# Longboard.net
KiCad netlist of a schematic drawn in EAGLE
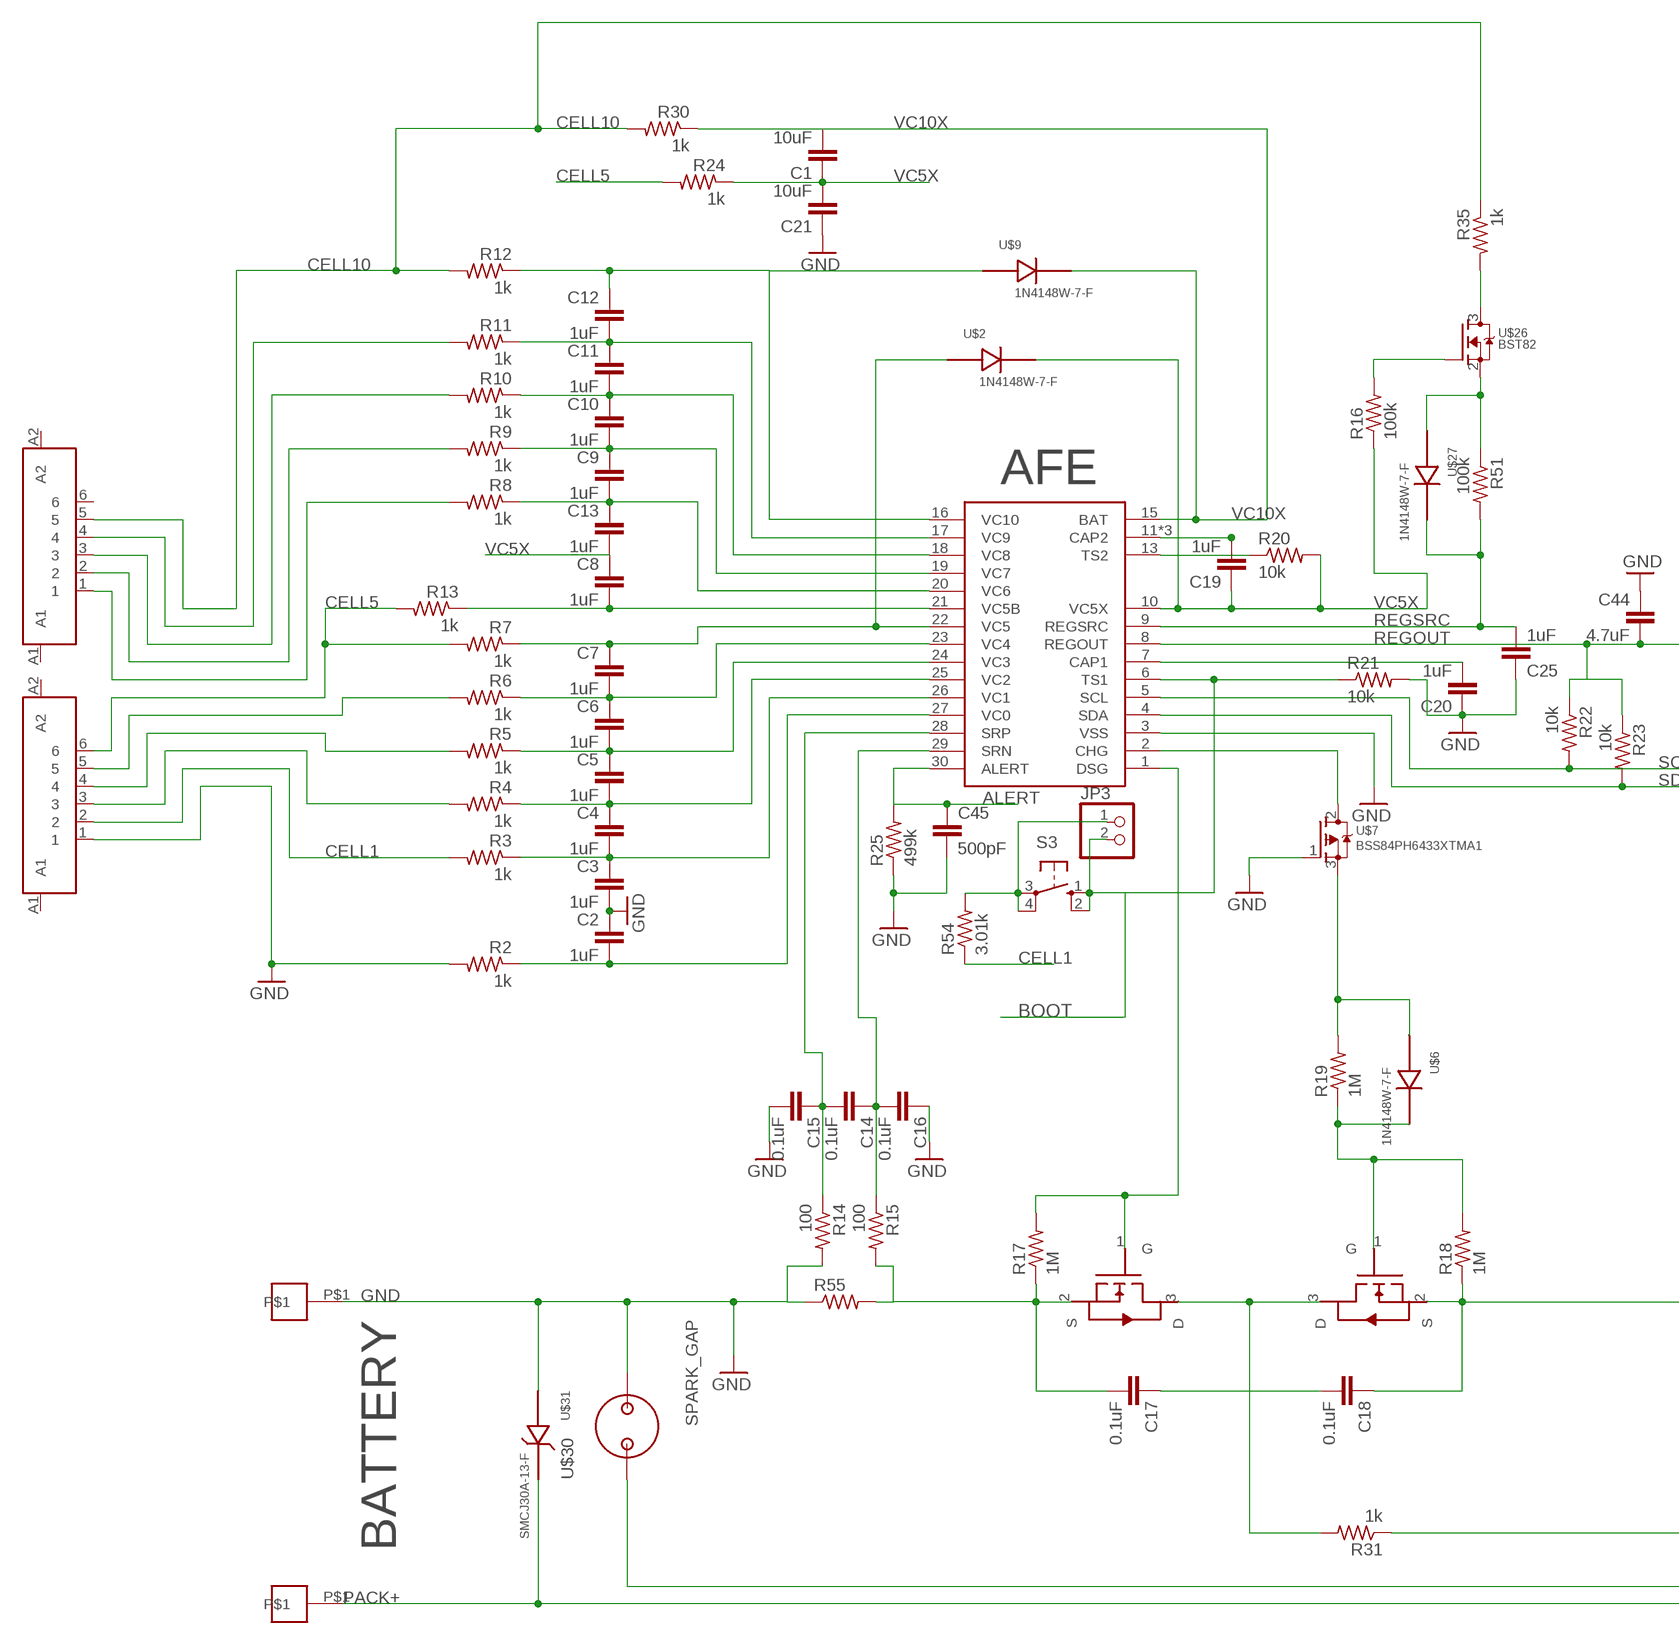
[diagram p0: schematic, sheet 1, part 1 of 2]
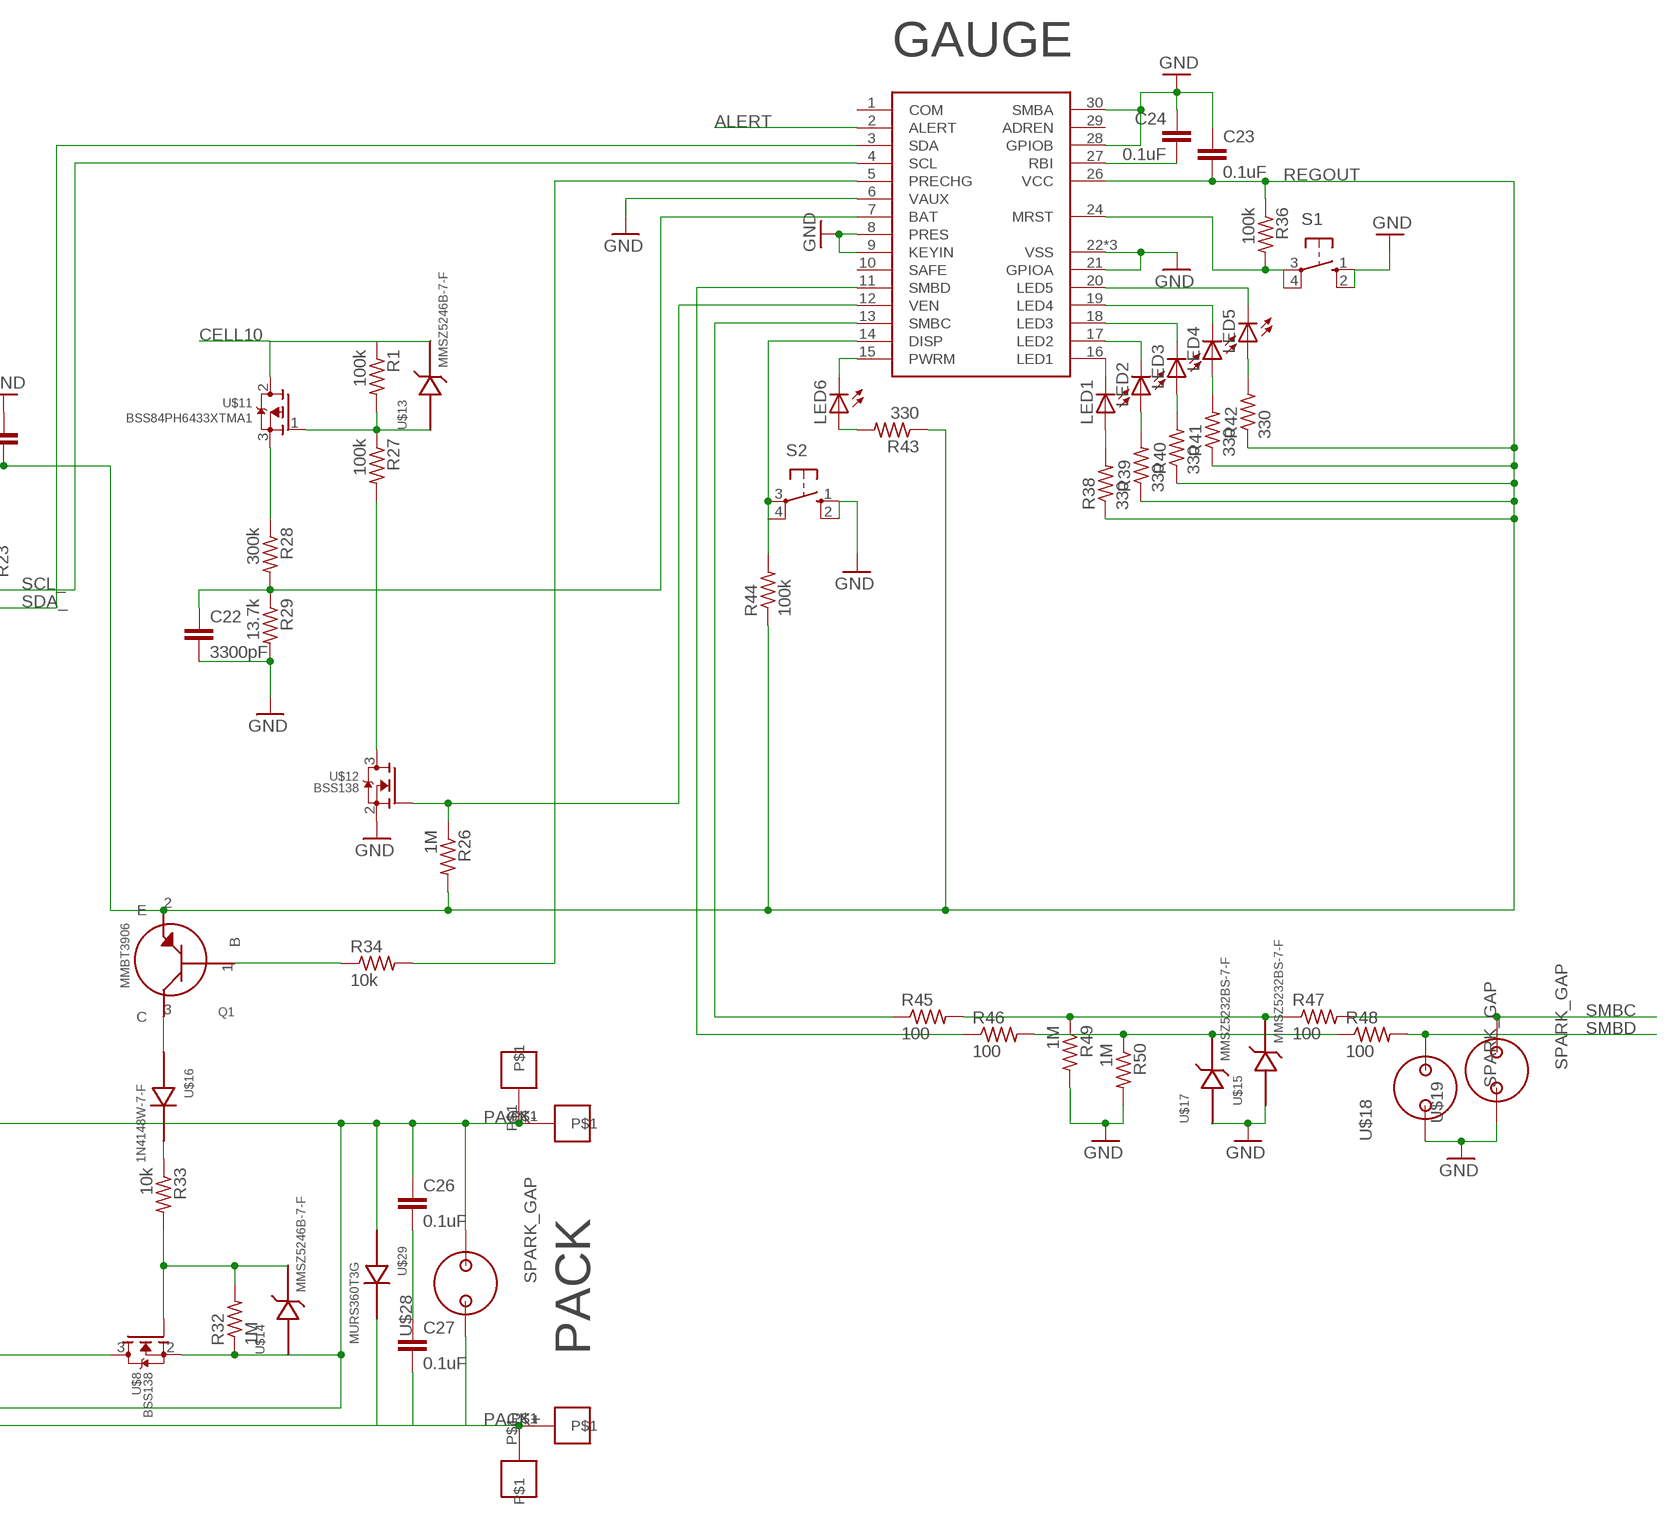
[diagram p1: schematic, sheet 1, part 2 of 2]
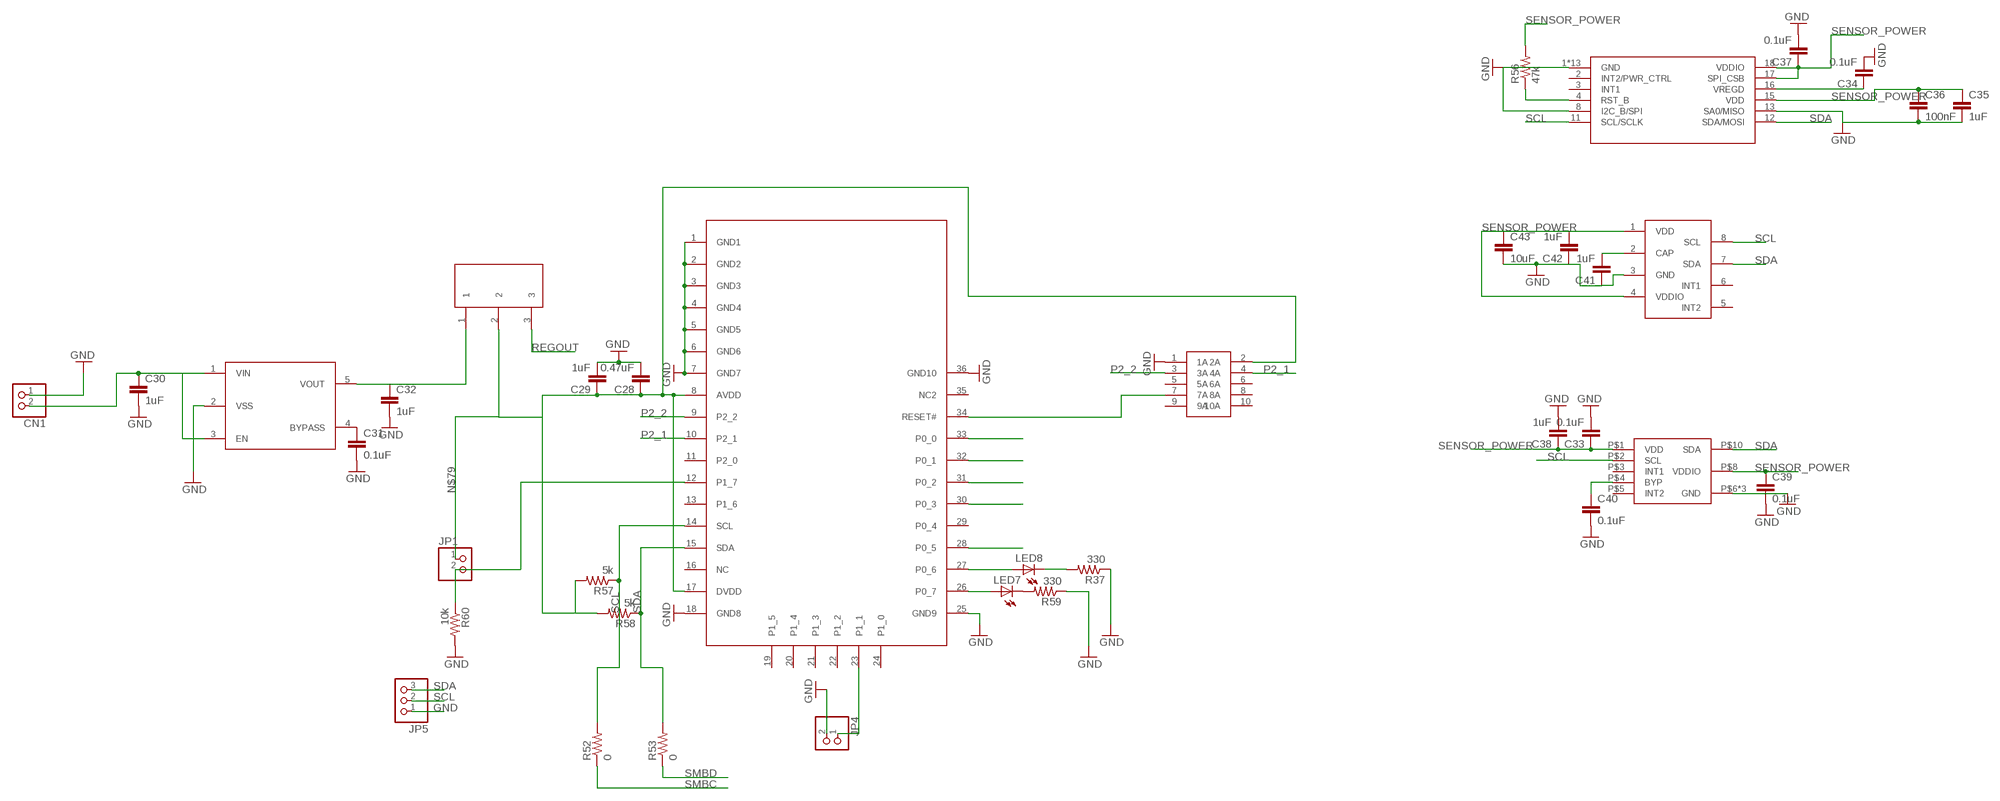
[diagram p2: schematic, sheet 2]

(export (version "E")
  (design (tool "Eeschema 10.0.6"))
  (components
    (comp (ref "C28")
      (value "0.47uF")
      (footprint "eagle-import:C0402")
      (libsource (lib "eagle-import") (part "C-EUC0402"))
    )
    (comp (ref "C29")
      (value "1uF")
      (footprint "eagle-import:C0402")
      (libsource (lib "eagle-import") (part "C-EUC0402"))
    )
    (comp (ref "C30")
      (value "1uF")
      (footprint "eagle-import:C0402")
      (libsource (lib "eagle-import") (part "C-EUC0402"))
    )
    (comp (ref "C31")
      (value "0.1uF")
      (footprint "eagle-import:C0402")
      (libsource (lib "eagle-import") (part "C-EUC0402"))
    )
    (comp (ref "C32")
      (value "1uF")
      (footprint "eagle-import:C0402")
      (libsource (lib "eagle-import") (part "C-EUC0402"))
    )
    (comp (ref "C33")
      (value "0.1uF")
      (footprint "eagle-import:C0402")
      (libsource (lib "eagle-import") (part "C-EUC0402"))
    )
    (comp (ref "C34")
      (value "0.1uF")
      (footprint "eagle-import:C0402")
      (libsource (lib "eagle-import") (part "C-EUC0402"))
    )
    (comp (ref "C35")
      (value "1uF")
      (footprint "eagle-import:C0402")
      (libsource (lib "eagle-import") (part "C-EUC0402"))
    )
    (comp (ref "C36")
      (value "100nF")
      (footprint "eagle-import:C0402")
      (libsource (lib "eagle-import") (part "C-EUC0402"))
    )
    (comp (ref "C37")
      (value "0.1uF")
      (footprint "eagle-import:C0402")
      (libsource (lib "eagle-import") (part "C-EUC0402"))
    )
    (comp (ref "C38")
      (value "1uF")
      (footprint "eagle-import:C0402")
      (libsource (lib "eagle-import") (part "C-EUC0402"))
    )
    (comp (ref "C39")
      (value "0.1uF")
      (footprint "eagle-import:C0402")
      (libsource (lib "eagle-import") (part "C-EUC0402"))
    )
    (comp (ref "C40")
      (value "0.1uF")
      (footprint "eagle-import:C0402")
      (libsource (lib "eagle-import") (part "C-EUC0402"))
    )
    (comp (ref "C41")
      (value "1uF")
      (footprint "eagle-import:C0402")
      (libsource (lib "eagle-import") (part "C-EUC0402"))
    )
    (comp (ref "C42")
      (value "1uF")
      (footprint "eagle-import:C0402")
      (libsource (lib "eagle-import") (part "C-EUC0402"))
    )
    (comp (ref "C43")
      (value "10uF")
      (footprint "eagle-import:C0603")
      (libsource (lib "eagle-import") (part "C-EUC0603"))
    )
    (comp (ref "CN1")
      (value "JST_2PIN-THM")
      (footprint "eagle-import:JST-PH-2-THM")
      (libsource (lib "eagle-import") (part "JST_2PIN-THM"))
    )
    (comp (ref "JP1")
      (value "PINHD-1X2")
      (footprint "eagle-import:1X02")
      (libsource (lib "eagle-import") (part "PINHD-1X2"))
    )
    (comp (ref "JP4")
      (value "PINHD-1X2")
      (footprint "eagle-import:1X02")
      (libsource (lib "eagle-import") (part "PINHD-1X2"))
    )
    (comp (ref "JP5")
      (value "PINHD-1X3")
      (footprint "eagle-import:1X03")
      (libsource (lib "eagle-import") (part "PINHD-1X3"))
    )
    (comp (ref "LED7")
      (value "LEDCHIP-LED0603")
      (footprint "eagle-import:CHIP-LED0603")
      (libsource (lib "eagle-import") (part "LEDCHIP-LED0603"))
    )
    (comp (ref "LED8")
      (value "LEDCHIP-LED0603")
      (footprint "eagle-import:CHIP-LED0603")
      (libsource (lib "eagle-import") (part "LEDCHIP-LED0603"))
    )
    (comp (ref "R37")
      (value "330")
      (footprint "eagle-import:R0402")
      (libsource (lib "eagle-import") (part "R-US_R0402"))
    )
    (comp (ref "R52")
      (value "0")
      (footprint "eagle-import:R0201")
      (libsource (lib "eagle-import") (part "R-US_R0201"))
    )
    (comp (ref "R53")
      (value "0")
      (footprint "eagle-import:R0201")
      (libsource (lib "eagle-import") (part "R-US_R0201"))
    )
    (comp (ref "R56")
      (value "47k")
      (footprint "eagle-import:R0402")
      (libsource (lib "eagle-import") (part "R-US_R0402"))
    )
    (comp (ref "R57")
      (value "5k")
      (footprint "eagle-import:R0402")
      (libsource (lib "eagle-import") (part "R-US_R0402"))
    )
    (comp (ref "R58")
      (value "5k")
      (footprint "eagle-import:R0402")
      (libsource (lib "eagle-import") (part "R-US_R0402"))
    )
    (comp (ref "R59")
      (value "330")
      (footprint "eagle-import:R0402")
      (libsource (lib "eagle-import") (part "R-US_R0402"))
    )
    (comp (ref "R60")
      (value "10k")
      (footprint "eagle-import:R0402")
      (libsource (lib "eagle-import") (part "R-US_R0402"))
    )
    (comp (ref "U$20")
      (value "BLE113")
      (footprint "eagle-import:BLUEGIGA")
      (libsource (lib "eagle-import") (part "BLE113"))
    )
    (comp (ref "U$21")
      (value "LP3985")
      (footprint "eagle-import:SOT23-5L")
      (libsource (lib "eagle-import") (part "LP3985"))
    )
    (comp (ref "U$22")
      (value "RIBBON_10POS_MALE")
      (footprint "eagle-import:RIBBON_10POS_MALE")
      (libsource (lib "eagle-import") (part "RIBBON_10POS_MALE"))
    )
    (comp (ref "U$23")
      (value "SPDT_THRU")
      (footprint "eagle-import:SPDT_THRU")
      (libsource (lib "eagle-import") (part "SPDT_THRU"))
    )
    (comp (ref "U$25")
      (value "MLP3115A2")
      (footprint "eagle-import:MLP3115A2")
      (libsource (lib "eagle-import") (part "MLP3115A2"))
    )
    (comp (ref "U$32")
      (value "MMA8653FC")
      (footprint "eagle-import:10-DFN2X2")
      (libsource (lib "eagle-import") (part "MMA8653FC"))
    )
    (comp (ref "U$34")
      (value "FXAS21002")
      (footprint "eagle-import:FXAS21002")
      (libsource (lib "eagle-import") (part "FXAS21002"))
    )
    (comp (ref "C1")
      (value "10uF")
      (footprint "eagle-import:C1210")
      (libsource (lib "eagle-import") (part "C-EUC1210"))
    )
    (comp (ref "C2")
      (value "1uF")
      (footprint "eagle-import:C0805")
      (libsource (lib "eagle-import") (part "C-EUC0805"))
    )
    (comp (ref "C3")
      (value "1uF")
      (footprint "eagle-import:C0805")
      (libsource (lib "eagle-import") (part "C-EUC0805"))
    )
    (comp (ref "C4")
      (value "1uF")
      (footprint "eagle-import:C0805")
      (libsource (lib "eagle-import") (part "C-EUC0805"))
    )
    (comp (ref "C5")
      (value "1uF")
      (footprint "eagle-import:C0805")
      (libsource (lib "eagle-import") (part "C-EUC0805"))
    )
    (comp (ref "C6")
      (value "1uF")
      (footprint "eagle-import:C0805")
      (libsource (lib "eagle-import") (part "C-EUC0805"))
    )
    (comp (ref "C7")
      (value "1uF")
      (footprint "eagle-import:C0805")
      (libsource (lib "eagle-import") (part "C-EUC0805"))
    )
    (comp (ref "C8")
      (value "1uF")
      (footprint "eagle-import:C0805")
      (libsource (lib "eagle-import") (part "C-EUC0805"))
    )
    (comp (ref "C9")
      (value "1uF")
      (footprint "eagle-import:C0805")
      (libsource (lib "eagle-import") (part "C-EUC0805"))
    )
    (comp (ref "C10")
      (value "1uF")
      (footprint "eagle-import:C0805")
      (libsource (lib "eagle-import") (part "C-EUC0805"))
    )
    (comp (ref "C11")
      (value "1uF")
      (footprint "eagle-import:C0805")
      (libsource (lib "eagle-import") (part "C-EUC0805"))
    )
    (comp (ref "C12")
      (value "1uF")
      (footprint "eagle-import:C0805")
      (libsource (lib "eagle-import") (part "C-EUC0805"))
    )
    (comp (ref "C13")
      (value "1uF")
      (footprint "eagle-import:C0805")
      (libsource (lib "eagle-import") (part "C-EUC0805"))
    )
    (comp (ref "C14")
      (value "0.1uF")
      (footprint "eagle-import:C0805")
      (libsource (lib "eagle-import") (part "C-EUC0805"))
    )
    (comp (ref "C15")
      (value "0.1uF")
      (footprint "eagle-import:C0805")
      (libsource (lib "eagle-import") (part "C-EUC0805"))
    )
    (comp (ref "C16")
      (value "0.1uF")
      (footprint "eagle-import:C0805")
      (libsource (lib "eagle-import") (part "C-EUC0805"))
    )
    (comp (ref "C17")
      (value "0.1uF")
      (footprint "eagle-import:C0805")
      (libsource (lib "eagle-import") (part "C-EUC0805"))
    )
    (comp (ref "C18")
      (value "0.1uF")
      (footprint "eagle-import:C0805")
      (libsource (lib "eagle-import") (part "C-EUC0805"))
    )
    (comp (ref "C19")
      (value "1uF")
      (footprint "eagle-import:C0805")
      (libsource (lib "eagle-import") (part "C-EUC0805"))
    )
    (comp (ref "C20")
      (value "1uF")
      (footprint "eagle-import:C0805")
      (libsource (lib "eagle-import") (part "C-EUC0805"))
    )
    (comp (ref "C21")
      (value "10uF")
      (footprint "eagle-import:C1210")
      (libsource (lib "eagle-import") (part "C-EUC1210"))
    )
    (comp (ref "C22")
      (value "3300pF")
      (footprint "eagle-import:C0402")
      (libsource (lib "eagle-import") (part "C-EUC0402"))
    )
    (comp (ref "C23")
      (value "0.1uF")
      (footprint "eagle-import:C0805")
      (libsource (lib "eagle-import") (part "C-EUC0805"))
    )
    (comp (ref "C24")
      (value "0.1uF")
      (footprint "eagle-import:C0805")
      (libsource (lib "eagle-import") (part "C-EUC0805"))
    )
    (comp (ref "C25")
      (value "1uF")
      (footprint "eagle-import:C0805")
      (libsource (lib "eagle-import") (part "C-EUC0805"))
    )
    (comp (ref "C26")
      (value "0.1uF")
      (footprint "eagle-import:C0805")
      (libsource (lib "eagle-import") (part "C-EUC0805"))
    )
    (comp (ref "C27")
      (value "0.1uF")
      (footprint "eagle-import:C0805")
      (libsource (lib "eagle-import") (part "C-EUC0805"))
    )
    (comp (ref "C44")
      (value "4.7uF")
      (footprint "eagle-import:C0805")
      (libsource (lib "eagle-import") (part "C-EUC0805"))
    )
    (comp (ref "C45")
      (value "500pF")
      (footprint "eagle-import:C0603")
      (libsource (lib "eagle-import") (part "C-EUC0603"))
    )
    (comp (ref "JP3")
      (value "PINHD-1X2")
      (footprint "eagle-import:1X02")
      (libsource (lib "eagle-import") (part "PINHD-1X2"))
    )
    (comp (ref "LED1")
      (value "LEDCHIPLED_0603")
      (footprint "eagle-import:CHIPLED_0603")
      (libsource (lib "eagle-import") (part "LEDCHIPLED_0603"))
    )
    (comp (ref "LED2")
      (value "LEDCHIPLED_0603")
      (footprint "eagle-import:CHIPLED_0603")
      (libsource (lib "eagle-import") (part "LEDCHIPLED_0603"))
    )
    (comp (ref "LED3")
      (value "LEDCHIPLED_0603")
      (footprint "eagle-import:CHIPLED_0603")
      (libsource (lib "eagle-import") (part "LEDCHIPLED_0603"))
    )
    (comp (ref "LED4")
      (value "LEDCHIPLED_0603")
      (footprint "eagle-import:CHIPLED_0603")
      (libsource (lib "eagle-import") (part "LEDCHIPLED_0603"))
    )
    (comp (ref "LED5")
      (value "LEDCHIPLED_0603")
      (footprint "eagle-import:CHIPLED_0603")
      (libsource (lib "eagle-import") (part "LEDCHIPLED_0603"))
    )
    (comp (ref "LED6")
      (value "LEDCHIPLED_0603")
      (footprint "eagle-import:CHIPLED_0603")
      (libsource (lib "eagle-import") (part "LEDCHIPLED_0603"))
    )
    (comp (ref "Q1")
      (value "MMBT3906")
      (footprint "eagle-import:SOT23-3")
      (libsource (lib "eagle-import") (part "MMBT3906"))
    )
    (comp (ref "R1")
      (value "100k")
      (footprint "eagle-import:R0805")
      (libsource (lib "eagle-import") (part "R-US_R0805"))
    )
    (comp (ref "R2")
      (value "1k")
      (footprint "eagle-import:R1206")
      (libsource (lib "eagle-import") (part "R-US_R1206"))
    )
    (comp (ref "R3")
      (value "1k")
      (footprint "eagle-import:R1206")
      (libsource (lib "eagle-import") (part "R-US_R1206"))
    )
    (comp (ref "R4")
      (value "1k")
      (footprint "eagle-import:R1206")
      (libsource (lib "eagle-import") (part "R-US_R1206"))
    )
    (comp (ref "R5")
      (value "1k")
      (footprint "eagle-import:R1206")
      (libsource (lib "eagle-import") (part "R-US_R1206"))
    )
    (comp (ref "R6")
      (value "1k")
      (footprint "eagle-import:R1206")
      (libsource (lib "eagle-import") (part "R-US_R1206"))
    )
    (comp (ref "R7")
      (value "1k")
      (footprint "eagle-import:R1206")
      (libsource (lib "eagle-import") (part "R-US_R1206"))
    )
    (comp (ref "R8")
      (value "1k")
      (footprint "eagle-import:R1206")
      (libsource (lib "eagle-import") (part "R-US_R1206"))
    )
    (comp (ref "R9")
      (value "1k")
      (footprint "eagle-import:R1206")
      (libsource (lib "eagle-import") (part "R-US_R1206"))
    )
    (comp (ref "R10")
      (value "1k")
      (footprint "eagle-import:R1206")
      (libsource (lib "eagle-import") (part "R-US_R1206"))
    )
    (comp (ref "R11")
      (value "1k")
      (footprint "eagle-import:R1206")
      (libsource (lib "eagle-import") (part "R-US_R1206"))
    )
    (comp (ref "R12")
      (value "1k")
      (footprint "eagle-import:R1206")
      (libsource (lib "eagle-import") (part "R-US_R1206"))
    )
    (comp (ref "R13")
      (value "1k")
      (footprint "eagle-import:R1206")
      (libsource (lib "eagle-import") (part "R-US_R1206"))
    )
    (comp (ref "R14")
      (value "100")
      (footprint "eagle-import:R0805")
      (libsource (lib "eagle-import") (part "R-US_R0805"))
    )
    (comp (ref "R15")
      (value "100")
      (footprint "eagle-import:R0805")
      (libsource (lib "eagle-import") (part "R-US_R0805"))
    )
    (comp (ref "R16")
      (value "100k")
      (footprint "eagle-import:R0805")
      (libsource (lib "eagle-import") (part "R-US_R0805"))
    )
    (comp (ref "R17")
      (value "1M")
      (footprint "eagle-import:R1206")
      (libsource (lib "eagle-import") (part "R-US_R1206"))
    )
    (comp (ref "R18")
      (value "1M")
      (footprint "eagle-import:R1206")
      (libsource (lib "eagle-import") (part "R-US_R1206"))
    )
    (comp (ref "R19")
      (value "1M")
      (footprint "eagle-import:R1206")
      (libsource (lib "eagle-import") (part "R-US_R1206"))
    )
    (comp (ref "R20")
      (value "10k")
      (footprint "eagle-import:R0805")
      (libsource (lib "eagle-import") (part "R-US_R0805"))
    )
    (comp (ref "R21")
      (value "10k")
      (footprint "eagle-import:R0805")
      (libsource (lib "eagle-import") (part "R-US_R0805"))
    )
    (comp (ref "R22")
      (value "10k")
      (footprint "eagle-import:R0805")
      (libsource (lib "eagle-import") (part "R-US_R0805"))
    )
    (comp (ref "R23")
      (value "10k")
      (footprint "eagle-import:R0805")
      (libsource (lib "eagle-import") (part "R-US_R0805"))
    )
    (comp (ref "R24")
      (value "1k")
      (footprint "eagle-import:R1206")
      (libsource (lib "eagle-import") (part "R-US_R1206"))
    )
    (comp (ref "R25")
      (value "499k")
      (footprint "eagle-import:R0603")
      (libsource (lib "eagle-import") (part "R-US_R0603"))
    )
    (comp (ref "R26")
      (value "1M")
      (footprint "eagle-import:R1206")
      (libsource (lib "eagle-import") (part "R-US_R1206"))
    )
    (comp (ref "R27")
      (value "100k")
      (footprint "eagle-import:R0805")
      (libsource (lib "eagle-import") (part "R-US_R0805"))
    )
    (comp (ref "R28")
      (value "300k")
      (footprint "eagle-import:R0805")
      (libsource (lib "eagle-import") (part "R-US_R0805"))
    )
    (comp (ref "R29")
      (value "13.7k")
      (footprint "eagle-import:R0805")
      (libsource (lib "eagle-import") (part "R-US_R0805"))
    )
    (comp (ref "R30")
      (value "1k")
      (footprint "eagle-import:R1206")
      (libsource (lib "eagle-import") (part "R-US_R1206"))
    )
    (comp (ref "R31")
      (value "1k")
      (footprint "eagle-import:R2512")
      (libsource (lib "eagle-import") (part "R-US_R2512"))
    )
    (comp (ref "R32")
      (value "1M")
      (footprint "eagle-import:R1206")
      (libsource (lib "eagle-import") (part "R-US_R1206"))
    )
    (comp (ref "R33")
      (value "10k")
      (footprint "eagle-import:R0805")
      (libsource (lib "eagle-import") (part "R-US_R0805"))
    )
    (comp (ref "R34")
      (value "10k")
      (footprint "eagle-import:R0805")
      (libsource (lib "eagle-import") (part "R-US_R0805"))
    )
    (comp (ref "R35")
      (value "1k")
      (footprint "eagle-import:R1206")
      (libsource (lib "eagle-import") (part "R-US_R1206"))
    )
    (comp (ref "R36")
      (value "100k")
      (footprint "eagle-import:R0805")
      (libsource (lib "eagle-import") (part "R-US_R0805"))
    )
    (comp (ref "R38")
      (value "330")
      (footprint "eagle-import:R0402")
      (libsource (lib "eagle-import") (part "R-US_R0402"))
    )
    (comp (ref "R39")
      (value "330")
      (footprint "eagle-import:R0402")
      (libsource (lib "eagle-import") (part "R-US_R0402"))
    )
    (comp (ref "R40")
      (value "330")
      (footprint "eagle-import:R0402")
      (libsource (lib "eagle-import") (part "R-US_R0402"))
    )
    (comp (ref "R41")
      (value "330")
      (footprint "eagle-import:R0402")
      (libsource (lib "eagle-import") (part "R-US_R0402"))
    )
    (comp (ref "R42")
      (value "330")
      (footprint "eagle-import:R0402")
      (libsource (lib "eagle-import") (part "R-US_R0402"))
    )
    (comp (ref "R43")
      (value "330")
      (footprint "eagle-import:R0402")
      (libsource (lib "eagle-import") (part "R-US_R0402"))
    )
    (comp (ref "R44")
      (value "100k")
      (footprint "eagle-import:R0402")
      (libsource (lib "eagle-import") (part "R-US_R0402"))
    )
    (comp (ref "R45")
      (value "100")
      (footprint "eagle-import:R0805")
      (libsource (lib "eagle-import") (part "R-US_R0805"))
    )
    (comp (ref "R46")
      (value "100")
      (footprint "eagle-import:R0805")
      (libsource (lib "eagle-import") (part "R-US_R0805"))
    )
    (comp (ref "R47")
      (value "100")
      (footprint "eagle-import:R0805")
      (libsource (lib "eagle-import") (part "R-US_R0805"))
    )
    (comp (ref "R48")
      (value "100")
      (footprint "eagle-import:R0805")
      (libsource (lib "eagle-import") (part "R-US_R0805"))
    )
    (comp (ref "R49")
      (value "1M")
      (footprint "eagle-import:R1206")
      (libsource (lib "eagle-import") (part "R-US_R1206"))
    )
    (comp (ref "R50")
      (value "1M")
      (footprint "eagle-import:R1206")
      (libsource (lib "eagle-import") (part "R-US_R1206"))
    )
    (comp (ref "R51")
      (value "100k")
      (footprint "eagle-import:R0805")
      (libsource (lib "eagle-import") (part "R-US_R0805"))
    )
    (comp (ref "R54")
      (value "3.01k")
      (footprint "eagle-import:R1206")
      (libsource (lib "eagle-import") (part "R-US_R1206"))
    )
    (comp (ref "R55")
      (value "R-US_R2512")
      (footprint "eagle-import:R2512")
      (libsource (lib "eagle-import") (part "R-US_R2512"))
    )
    (comp (ref "S1")
      (value "10-XX")
      (footprint "eagle-import:B3F-10XX")
      (fields (field (name "MPN") "B3F-1000"))
      (libsource (lib "eagle-import") (part "10-XX"))
    )
    (comp (ref "S2")
      (value "10-XX")
      (footprint "eagle-import:B3F-10XX")
      (fields (field (name "MPN") "B3F-1000"))
      (libsource (lib "eagle-import") (part "10-XX"))
    )
    (comp (ref "S3")
      (value "10-XX")
      (footprint "eagle-import:B3F-10XX")
      (fields (field (name "MPN") "B3F-1000"))
      (libsource (lib "eagle-import") (part "10-XX"))
    )
    (comp (ref "U$1")
      (value "BQ76930")
      (footprint "eagle-import:SOIC-30")
      (libsource (lib "eagle-import") (part "BQ76930"))
    )
    (comp (ref "U$2")
      (value "1N4148W-7-F")
      (footprint "eagle-import:SOD-123")
      (libsource (lib "eagle-import") (part "1N4148W-7-F"))
    )
    (comp (ref "U$3")
      (value "PAD")
      (footprint "eagle-import:PAD")
      (libsource (lib "eagle-import") (part "PAD"))
    )
    (comp (ref "U$4")
      (value "AOB290L")
      (footprint "eagle-import:TO-263")
      (libsource (lib "eagle-import") (part "AOB290L"))
    )
    (comp (ref "U$5")
      (value "AOB290L")
      (footprint "eagle-import:TO-263")
      (libsource (lib "eagle-import") (part "AOB290L"))
    )
    (comp (ref "U$6")
      (value "1N4148W-7-F")
      (footprint "eagle-import:SOD-123")
      (libsource (lib "eagle-import") (part "1N4148W-7-F"))
    )
    (comp (ref "U$7")
      (value "BSS84PH6433XTMA1")
      (footprint "eagle-import:SOT23-3")
      (libsource (lib "eagle-import") (part "BSS84PH6433XTMA1"))
    )
    (comp (ref "U$8")
      (value "BSS138")
      (footprint "eagle-import:SOT23-3")
      (libsource (lib "eagle-import") (part "BSS138"))
    )
    (comp (ref "U$9")
      (value "1N4148W-7-F")
      (footprint "eagle-import:SOD-123")
      (libsource (lib "eagle-import") (part "1N4148W-7-F"))
    )
    (comp (ref "U$10")
      (value "BQ78350-R1")
      (footprint "eagle-import:SOIC-30")
      (libsource (lib "eagle-import") (part "BQ78350-R1"))
    )
    (comp (ref "U$11")
      (value "BSS84PH6433XTMA1")
      (footprint "eagle-import:SOT23-3")
      (libsource (lib "eagle-import") (part "BSS84PH6433XTMA1"))
    )
    (comp (ref "U$12")
      (value "BSS138")
      (footprint "eagle-import:SOT23-3")
      (libsource (lib "eagle-import") (part "BSS138"))
    )
    (comp (ref "U$13")
      (value "MMSZ5246B-7-F")
      (footprint "eagle-import:SOD-123")
      (libsource (lib "eagle-import") (part "MMSZ5246B-7-F"))
    )
    (comp (ref "U$14")
      (value "MMSZ5246B-7-F")
      (footprint "eagle-import:SOD-123")
      (libsource (lib "eagle-import") (part "MMSZ5246B-7-F"))
    )
    (comp (ref "U$15")
      (value "MMSZ5232BS-7-F")
      (footprint "eagle-import:SOD-323F")
      (libsource (lib "eagle-import") (part "MMSZ5232BS-7-F"))
    )
    (comp (ref "U$16")
      (value "1N4148W-7-F")
      (footprint "eagle-import:SOD-123")
      (libsource (lib "eagle-import") (part "1N4148W-7-F"))
    )
    (comp (ref "U$17")
      (value "MMSZ5232BS-7-F")
      (footprint "eagle-import:SOD-323F")
      (libsource (lib "eagle-import") (part "MMSZ5232BS-7-F"))
    )
    (comp (ref "U$18")
      (value "SPARK_GAP")
      (footprint "eagle-import:SPARK_GAP")
      (libsource (lib "eagle-import") (part "SPARK_GAP"))
    )
    (comp (ref "U$19")
      (value "SPARK_GAP")
      (footprint "eagle-import:SPARK_GAP")
      (libsource (lib "eagle-import") (part "SPARK_GAP"))
    )
    (comp (ref "U$24")
      (value "JST_6PIN")
      (footprint "eagle-import:JST_6PIN")
      (libsource (lib "eagle-import") (part "JST_6PIN"))
    )
    (comp (ref "U$26")
      (value "BST82")
      (footprint "eagle-import:SOT23-3")
      (libsource (lib "eagle-import") (part "BST82"))
    )
    (comp (ref "U$27")
      (value "1N4148W-7-F")
      (footprint "eagle-import:SOD-123")
      (libsource (lib "eagle-import") (part "1N4148W-7-F"))
    )
    (comp (ref "U$28")
      (value "SPARK_GAP")
      (footprint "eagle-import:SPARK_GAP")
      (libsource (lib "eagle-import") (part "SPARK_GAP"))
    )
    (comp (ref "U$29")
      (value "MURS360T3G")
      (footprint "eagle-import:SMC(DO-214AB)")
      (libsource (lib "eagle-import") (part "MURS360T3G"))
    )
    (comp (ref "U$30")
      (value "SPARK_GAP")
      (footprint "eagle-import:SPARK_GAP")
      (libsource (lib "eagle-import") (part "SPARK_GAP"))
    )
    (comp (ref "U$31")
      (value "SMCJ30A-13-F")
      (footprint "eagle-import:SMB(DO-214AA)")
      (libsource (lib "eagle-import") (part "SMCJ30A-13-F"))
    )
    (comp (ref "U$33")
      (value "JST_6PIN")
      (footprint "eagle-import:JST_6PIN")
      (libsource (lib "eagle-import") (part "JST_6PIN"))
    )
    (comp (ref "U$35")
      (value "PAD")
      (footprint "eagle-import:PAD")
      (libsource (lib "eagle-import") (part "PAD"))
    )
    (comp (ref "U$36")
      (value "PAD")
      (footprint "eagle-import:PAD")
      (libsource (lib "eagle-import") (part "PAD"))
    )
    (comp (ref "U$37")
      (value "PAD")
      (footprint "eagle-import:PAD")
      (libsource (lib "eagle-import") (part "PAD"))
    )
    (comp (ref "U$38")
      (value "PAD")
      (footprint "eagle-import:PAD")
      (libsource (lib "eagle-import") (part "PAD"))
    )
    (comp (ref "U$39")
      (value "PAD")
      (footprint "eagle-import:PAD")
      (libsource (lib "eagle-import") (part "PAD"))
    )
  )
  (nets
    (net (code "1") (name "ALERT") (class "Default")
      (node (ref "C45") (pin "1") (pinfunction "1_1") (pintype "passive"))
      (node (ref "R25") (pin "2") (pinfunction "2_2") (pintype "passive"))
      (node (ref "U$1") (pin "30") (pinfunction "ALERT_30") (pintype "bidirectional"))
      (node (ref "U$10") (pin "2") (pinfunction "ALERT_2") (pintype "bidirectional"))
    )
    (net (code "2") (name "BOOT") (class "Default")
      (node (ref "JP3") (pin "2") (pinfunction "2_2") (pintype "passive"))
      (node (ref "R21") (pin "1") (pinfunction "1_1") (pintype "passive"))
      (node (ref "S3") (pin "1") (pinfunction "S_1") (pintype "passive"))
      (node (ref "S3") (pin "2") (pinfunction "S1_2") (pintype "passive"))
      (node (ref "U$1") (pin "6") (pinfunction "TS1_6") (pintype "bidirectional"))
    )
    (net (code "3") (name "CELL1") (class "Default")
      (node (ref "R3") (pin "2") (pinfunction "2_2") (pintype "passive"))
      (node (ref "R54") (pin "1") (pinfunction "1_1") (pintype "passive"))
      (node (ref "U$33") (pin "2") (pinfunction "2_2") (pintype "bidirectional"))
    )
    (net (code "4") (name "CELL5") (class "Default")
      (node (ref "R13") (pin "2") (pinfunction "2_2") (pintype "passive"))
      (node (ref "R24") (pin "2") (pinfunction "2_2") (pintype "passive"))
      (node (ref "R7") (pin "2") (pinfunction "2_2") (pintype "passive"))
      (node (ref "U$33") (pin "6") (pinfunction "6_6") (pintype "bidirectional"))
    )
    (net (code "5") (name "CELL10") (class "Default")
      (node (ref "R1") (pin "1") (pinfunction "1_1") (pintype "passive"))
      (node (ref "R12") (pin "2") (pinfunction "2_2") (pintype "passive"))
      (node (ref "R30") (pin "2") (pinfunction "2_2") (pintype "passive"))
      (node (ref "R35") (pin "1") (pinfunction "1_1") (pintype "passive"))
      (node (ref "U$11") (pin "2") (pinfunction "S_2") (pintype "bidirectional"))
      (node (ref "U$13") (pin "P$2") (pinfunction "2_P$2") (pintype "bidirectional"))
      (node (ref "U$24") (pin "5") (pinfunction "5_5") (pintype "bidirectional"))
    )
    (net (code "6") (name "GND") (class "Default")
      (node (ref "C15") (pin "2") (pinfunction "2_2") (pintype "passive"))
      (node (ref "C16") (pin "1") (pinfunction "1_1") (pintype "passive"))
      (node (ref "C2") (pin "1") (pinfunction "1_1") (pintype "passive"))
      (node (ref "C20") (pin "1") (pinfunction "1_1") (pintype "passive"))
      (node (ref "C21") (pin "1") (pinfunction "1_1") (pintype "passive"))
      (node (ref "C22") (pin "2") (pinfunction "2_2") (pintype "passive"))
      (node (ref "C23") (pin "1") (pinfunction "1_1") (pintype "passive"))
      (node (ref "C24") (pin "1") (pinfunction "1_1") (pintype "passive"))
      (node (ref "C25") (pin "1") (pinfunction "1_1") (pintype "passive"))
      (node (ref "C28") (pin "2") (pinfunction "2_2") (pintype "passive"))
      (node (ref "C29") (pin "2") (pinfunction "2_2") (pintype "passive"))
      (node (ref "C3") (pin "2") (pinfunction "2_2") (pintype "passive"))
      (node (ref "C30") (pin "2") (pinfunction "2_2") (pintype "passive"))
      (node (ref "C31") (pin "2") (pinfunction "2_2") (pintype "passive"))
      (node (ref "C32") (pin "2") (pinfunction "2_2") (pintype "passive"))
      (node (ref "C33") (pin "2") (pinfunction "2_2") (pintype "passive"))
      (node (ref "C34") (pin "2") (pinfunction "2_2") (pintype "passive"))
      (node (ref "C35") (pin "2") (pinfunction "2_2") (pintype "passive"))
      (node (ref "C36") (pin "2") (pinfunction "2_2") (pintype "passive"))
      (node (ref "C37") (pin "2") (pinfunction "2_2") (pintype "passive"))
      (node (ref "C38") (pin "2") (pinfunction "2_2") (pintype "passive"))
      (node (ref "C39") (pin "2") (pinfunction "2_2") (pintype "passive"))
      (node (ref "C40") (pin "2") (pinfunction "2_2") (pintype "passive"))
      (node (ref "C41") (pin "1") (pinfunction "1_1") (pintype "passive"))
      (node (ref "C42") (pin "1") (pinfunction "1_1") (pintype "passive"))
      (node (ref "C43") (pin "2") (pinfunction "2_2") (pintype "passive"))
      (node (ref "C44") (pin "1") (pinfunction "1_1") (pintype "passive"))
      (node (ref "C45") (pin "2") (pinfunction "2_2") (pintype "passive"))
      (node (ref "CN1") (pin "1") (pinfunction "2_1") (pintype "passive"))
      (node (ref "JP4") (pin "2") (pinfunction "2_2") (pintype "passive"))
      (node (ref "JP5") (pin "1") (pinfunction "1_1") (pintype "passive"))
      (node (ref "R14") (pin "2") (pinfunction "2_2") (pintype "passive"))
      (node (ref "R2") (pin "2") (pinfunction "2_2") (pintype "passive"))
      (node (ref "R21") (pin "2") (pinfunction "2_2") (pintype "passive"))
      (node (ref "R25") (pin "1") (pinfunction "1_1") (pintype "passive"))
      (node (ref "R29") (pin "2") (pinfunction "2_2") (pintype "passive"))
      (node (ref "R37") (pin "1") (pinfunction "1_1") (pintype "passive"))
      (node (ref "R49") (pin "2") (pinfunction "2_2") (pintype "passive"))
      (node (ref "R50") (pin "2") (pinfunction "2_2") (pintype "passive"))
      (node (ref "R55") (pin "1") (pinfunction "1_1") (pintype "passive"))
      (node (ref "R59") (pin "1") (pinfunction "1_1") (pintype "passive"))
      (node (ref "R60") (pin "2") (pinfunction "2_2") (pintype "passive"))
      (node (ref "S1") (pin "1") (pinfunction "S_1") (pintype "passive"))
      (node (ref "S1") (pin "2") (pinfunction "S1_2") (pintype "passive"))
      (node (ref "S2") (pin "1") (pinfunction "S_1") (pintype "passive"))
      (node (ref "S2") (pin "2") (pinfunction "S1_2") (pintype "passive"))
      (node (ref "U$1") (pin "3") (pinfunction "VSS_3") (pintype "bidirectional"))
      (node (ref "U$10") (pin "21") (pinfunction "GPIOA_21") (pintype "bidirectional"))
      (node (ref "U$10") (pin "22") (pinfunction "VSS_22") (pintype "bidirectional"))
      (node (ref "U$10") (pin "23") (pinfunction "VSS_23") (pintype "bidirectional"))
      (node (ref "U$10") (pin "25") (pinfunction "VSS_25") (pintype "bidirectional"))
      (node (ref "U$10") (pin "28") (pinfunction "GPIOB_28") (pintype "bidirectional"))
      (node (ref "U$10") (pin "30") (pinfunction "SMBA_30") (pintype "bidirectional"))
      (node (ref "U$10") (pin "6") (pinfunction "VAUX_6") (pintype "bidirectional"))
      (node (ref "U$10") (pin "8") (pinfunction "PRES_8") (pintype "bidirectional"))
      (node (ref "U$10") (pin "9") (pinfunction "KEYIN_9") (pintype "bidirectional"))
      (node (ref "U$12") (pin "2") (pinfunction "S_2") (pintype "bidirectional"))
      (node (ref "U$15") (pin "1") (pinfunction "1_1") (pintype "bidirectional"))
      (node (ref "U$17") (pin "1") (pinfunction "1_1") (pintype "bidirectional"))
      (node (ref "U$18") (pin "P$1") (pinfunction "P$1_P$1") (pintype "bidirectional"))
      (node (ref "U$19") (pin "P$1") (pinfunction "P$1_P$1") (pintype "bidirectional"))
      (node (ref "U$20") (pin "1") (pinfunction "GND1_1") (pintype "bidirectional"))
      (node (ref "U$20") (pin "18") (pinfunction "GND8_18") (pintype "bidirectional"))
      (node (ref "U$20") (pin "2") (pinfunction "GND2_2") (pintype "bidirectional"))
      (node (ref "U$20") (pin "25") (pinfunction "GND9_25") (pintype "bidirectional"))
      (node (ref "U$20") (pin "3") (pinfunction "GND3_3") (pintype "bidirectional"))
      (node (ref "U$20") (pin "36") (pinfunction "GND10_36") (pintype "bidirectional"))
      (node (ref "U$20") (pin "4") (pinfunction "GND4_4") (pintype "bidirectional"))
      (node (ref "U$20") (pin "5") (pinfunction "GND5_5") (pintype "bidirectional"))
      (node (ref "U$20") (pin "6") (pinfunction "GND6_6") (pintype "bidirectional"))
      (node (ref "U$20") (pin "7") (pinfunction "GND7_7") (pintype "bidirectional"))
      (node (ref "U$21") (pin "2") (pinfunction "VSS_2") (pintype "bidirectional"))
      (node (ref "U$22") (pin "1") (pinfunction "1A_1") (pintype "bidirectional"))
      (node (ref "U$25") (pin "3") (pinfunction "GND_3") (pintype "bidirectional"))
      (node (ref "U$3") (pin "P$1") (pinfunction "P$1_P$1") (pintype "bidirectional"))
      (node (ref "U$30") (pin "P$2") (pinfunction "P$2_P$2") (pintype "bidirectional"))
      (node (ref "U$31") (pin "P$1") (pinfunction "1_P$1") (pintype "bidirectional"))
      (node (ref "U$32") (pin "P$6") (pinfunction "GND_P$6") (pintype "bidirectional"))
      (node (ref "U$32") (pin "P$7") (pinfunction "GND_P$7") (pintype "bidirectional"))
      (node (ref "U$32") (pin "P$9") (pinfunction "GND_P$9") (pintype "bidirectional"))
      (node (ref "U$33") (pin "1") (pinfunction "1_1") (pintype "bidirectional"))
      (node (ref "U$34") (pin "1") (pinfunction "GND_1") (pintype "bidirectional"))
      (node (ref "U$34") (pin "10") (pinfunction "GND_10") (pintype "bidirectional"))
      (node (ref "U$34") (pin "13") (pinfunction "SA0/MISO_13") (pintype "bidirectional"))
      (node (ref "U$34") (pin "14") (pinfunction "GND_14") (pintype "bidirectional"))
      (node (ref "U$34") (pin "19") (pinfunction "GND_19") (pintype "bidirectional"))
      (node (ref "U$34") (pin "20") (pinfunction "GND_20") (pintype "bidirectional"))
      (node (ref "U$34") (pin "21") (pinfunction "GND_21") (pintype "bidirectional"))
      (node (ref "U$34") (pin "22") (pinfunction "GND_22") (pintype "bidirectional"))
      (node (ref "U$34") (pin "23") (pinfunction "GND_23") (pintype "bidirectional"))
      (node (ref "U$34") (pin "24") (pinfunction "GND_24") (pintype "bidirectional"))
      (node (ref "U$34") (pin "5") (pinfunction "GND_5") (pintype "bidirectional"))
      (node (ref "U$34") (pin "6") (pinfunction "GND_6") (pintype "bidirectional"))
      (node (ref "U$34") (pin "7") (pinfunction "GND_7") (pintype "bidirectional"))
      (node (ref "U$34") (pin "8") (pinfunction "I2C_B/SPI_8") (pintype "bidirectional"))
      (node (ref "U$34") (pin "9") (pinfunction "GND_9") (pintype "bidirectional"))
      (node (ref "U$7") (pin "1") (pinfunction "G_1") (pintype "bidirectional"))
    )
    (net (code "7") (name "N$79") (class "Default")
      (node (ref "C28") (pin "1") (pinfunction "1_1") (pintype "passive"))
      (node (ref "C29") (pin "1") (pinfunction "1_1") (pintype "passive"))
      (node (ref "JP1") (pin "1") (pinfunction "1_1") (pintype "passive"))
      (node (ref "R57") (pin "2") (pinfunction "2_2") (pintype "passive"))
      (node (ref "R58") (pin "2") (pinfunction "2_2") (pintype "passive"))
      (node (ref "U$20") (pin "17") (pinfunction "DVDD_17") (pintype "bidirectional"))
      (node (ref "U$20") (pin "8") (pinfunction "AVDD_8") (pintype "bidirectional"))
      (node (ref "U$22") (pin "2") (pinfunction "2A_2") (pintype "bidirectional"))
      (node (ref "U$23") (pin "2") (pinfunction "2_2") (pintype "bidirectional"))
    )
    (net (code "8") (name "Net-(C17-Pad1)") (class "Default")
      (node (ref "C17") (pin "1") (pinfunction "1_1") (pintype "passive"))
      (node (ref "C18") (pin "2") (pinfunction "2_2") (pintype "passive"))
    )
    (net (code "9") (name "Net-(C19-Pad2)") (class "Default")
      (node (ref "C19") (pin "2") (pinfunction "2_2") (pintype "passive"))
      (node (ref "U$1") (pin "11") (pinfunction "CAP2_11") (pintype "bidirectional"))
      (node (ref "U$1") (pin "12") (pinfunction "CAP2_12") (pintype "bidirectional"))
      (node (ref "U$1") (pin "14") (pinfunction "CAP2_14") (pintype "bidirectional"))
    )
    (net (code "10") (name "Net-(C26-Pad2)") (class "Default")
      (node (ref "C26") (pin "2") (pinfunction "2_2") (pintype "passive"))
      (node (ref "C27") (pin "1") (pinfunction "1_1") (pintype "passive"))
    )
    (net (code "11") (name "Net-(CN1-1)") (class "Default")
      (node (ref "C30") (pin "1") (pinfunction "1_1") (pintype "passive"))
      (node (ref "CN1") (pin "2") (pinfunction "1_2") (pintype "passive"))
      (node (ref "U$21") (pin "1") (pinfunction "VIN_1") (pintype "bidirectional"))
      (node (ref "U$21") (pin "3") (pinfunction "EN_3") (pintype "bidirectional"))
    )
    (net (code "12") (name "Net-(LED1-PadA)") (class "Default")
      (node (ref "LED1") (pin "A") (pinfunction "A_A") (pintype "passive"))
      (node (ref "R38") (pin "2") (pinfunction "2_2") (pintype "passive"))
    )
    (net (code "13") (name "Net-(LED2-PadA)") (class "Default")
      (node (ref "LED2") (pin "A") (pinfunction "A_A") (pintype "passive"))
      (node (ref "R39") (pin "2") (pinfunction "2_2") (pintype "passive"))
    )
    (net (code "14") (name "Net-(LED3-PadA)") (class "Default")
      (node (ref "LED3") (pin "A") (pinfunction "A_A") (pintype "passive"))
      (node (ref "R40") (pin "2") (pinfunction "2_2") (pintype "passive"))
    )
    (net (code "15") (name "Net-(LED4-PadA)") (class "Default")
      (node (ref "LED4") (pin "A") (pinfunction "A_A") (pintype "passive"))
      (node (ref "R41") (pin "2") (pinfunction "2_2") (pintype "passive"))
    )
    (net (code "16") (name "Net-(LED5-PadA)") (class "Default")
      (node (ref "LED5") (pin "A") (pinfunction "A_A") (pintype "passive"))
      (node (ref "R42") (pin "2") (pinfunction "2_2") (pintype "passive"))
    )
    (net (code "17") (name "Net-(LED6-PadA)") (class "Default")
      (node (ref "LED6") (pin "A") (pinfunction "A_A") (pintype "passive"))
      (node (ref "R43") (pin "2") (pinfunction "2_2") (pintype "passive"))
    )
    (net (code "18") (name "Net-(LED7-PadC)") (class "Default")
      (node (ref "LED7") (pin "C") (pinfunction "C_C") (pintype "passive"))
      (node (ref "R59") (pin "2") (pinfunction "2_2") (pintype "passive"))
    )
    (net (code "19") (name "Net-(LED8-PadC)") (class "Default")
      (node (ref "LED8") (pin "C") (pinfunction "C_C") (pintype "passive"))
      (node (ref "R37") (pin "2") (pinfunction "2_2") (pintype "passive"))
    )
    (net (code "20") (name "Net-(Q1-B)") (class "Default")
      (node (ref "Q1") (pin "1") (pinfunction "B_1") (pintype "bidirectional"))
      (node (ref "R34") (pin "1") (pinfunction "1_1") (pintype "passive"))
    )
    (net (code "21") (name "Net-(Q1-C)") (class "Default")
      (node (ref "Q1") (pin "3") (pinfunction "C_3") (pintype "bidirectional"))
      (node (ref "U$16") (pin "P$1") (pinfunction "P$1_P$1") (pintype "bidirectional"))
    )
    (net (code "22") (name "Net-(R4-Pad2)") (class "Default")
      (node (ref "R4") (pin "2") (pinfunction "2_2") (pintype "passive"))
      (node (ref "U$33") (pin "3") (pinfunction "3_3") (pintype "bidirectional"))
    )
    (net (code "23") (name "Net-(R5-Pad2)") (class "Default")
      (node (ref "R5") (pin "2") (pinfunction "2_2") (pintype "passive"))
      (node (ref "U$33") (pin "4") (pinfunction "4_4") (pintype "bidirectional"))
    )
    (net (code "24") (name "Net-(R6-Pad2)") (class "Default")
      (node (ref "R6") (pin "2") (pinfunction "2_2") (pintype "passive"))
      (node (ref "U$33") (pin "5") (pinfunction "5_5") (pintype "bidirectional"))
    )
    (net (code "25") (name "Net-(R8-Pad2)") (class "Default")
      (node (ref "R8") (pin "2") (pinfunction "2_2") (pintype "passive"))
      (node (ref "U$24") (pin "1") (pinfunction "1_1") (pintype "bidirectional"))
    )
    (net (code "26") (name "Net-(R9-Pad2)") (class "Default")
      (node (ref "R9") (pin "2") (pinfunction "2_2") (pintype "passive"))
      (node (ref "U$24") (pin "2") (pinfunction "2_2") (pintype "bidirectional"))
    )
    (net (code "27") (name "Net-(R10-Pad2)") (class "Default")
      (node (ref "R10") (pin "2") (pinfunction "2_2") (pintype "passive"))
      (node (ref "U$24") (pin "3") (pinfunction "3_3") (pintype "bidirectional"))
    )
    (net (code "28") (name "Net-(R11-Pad2)") (class "Default")
      (node (ref "R11") (pin "2") (pinfunction "2_2") (pintype "passive"))
      (node (ref "U$24") (pin "4") (pinfunction "4_4") (pintype "bidirectional"))
    )
    (net (code "29") (name "Net-(R33-Pad1)") (class "Default")
      (node (ref "R33") (pin "1") (pinfunction "1_1") (pintype "passive"))
      (node (ref "U$16") (pin "P$2") (pinfunction "P$2_P$2") (pintype "bidirectional"))
    )
    (net (code "30") (name "Net-(R45-Pad2)") (class "Default")
      (node (ref "R45") (pin "2") (pinfunction "2_2") (pintype "passive"))
      (node (ref "R47") (pin "1") (pinfunction "1_1") (pintype "passive"))
      (node (ref "R49") (pin "1") (pinfunction "1_1") (pintype "passive"))
      (node (ref "U$15") (pin "2") (pinfunction "2_2") (pintype "bidirectional"))
    )
    (net (code "31") (name "Net-(R46-Pad2)") (class "Default")
      (node (ref "R46") (pin "2") (pinfunction "2_2") (pintype "passive"))
      (node (ref "R48") (pin "1") (pinfunction "1_1") (pintype "passive"))
      (node (ref "R50") (pin "1") (pinfunction "1_1") (pintype "passive"))
      (node (ref "U$17") (pin "2") (pinfunction "2_2") (pintype "bidirectional"))
    )
    (net (code "32") (name "Net-(S1-P)") (class "Default")
      (node (ref "R36") (pin "2") (pinfunction "2_2") (pintype "passive"))
      (node (ref "S1") (pin "3") (pinfunction "P_3") (pintype "passive"))
      (node (ref "S1") (pin "4") (pinfunction "P1_4") (pintype "passive"))
      (node (ref "U$10") (pin "24") (pinfunction "MRST_24") (pintype "bidirectional"))
    )
    (net (code "33") (name "Net-(S2-P)") (class "Default")
      (node (ref "R44") (pin "2") (pinfunction "2_2") (pintype "passive"))
      (node (ref "S2") (pin "3") (pinfunction "P_3") (pintype "passive"))
      (node (ref "S2") (pin "4") (pinfunction "P1_4") (pintype "passive"))
      (node (ref "U$10") (pin "14") (pinfunction "DISP_14") (pintype "bidirectional"))
    )
    (net (code "34") (name "Net-(S3-P)") (class "Default")
      (node (ref "JP3") (pin "1") (pinfunction "1_1") (pintype "passive"))
      (node (ref "R54") (pin "2") (pinfunction "2_2") (pintype "passive"))
      (node (ref "S3") (pin "3") (pinfunction "P_3") (pintype "passive"))
      (node (ref "S3") (pin "4") (pinfunction "P1_4") (pintype "passive"))
    )
    (net (code "35") (name "Net-(U$1-CAP1)") (class "Default")
      (node (ref "C20") (pin "2") (pinfunction "2_2") (pintype "passive"))
      (node (ref "U$1") (pin "7") (pinfunction "CAP1_7") (pintype "bidirectional"))
    )
    (net (code "36") (name "Net-(U$1-CHG)") (class "Default")
      (node (ref "U$1") (pin "2") (pinfunction "CHG_2") (pintype "bidirectional"))
      (node (ref "U$7") (pin "2") (pinfunction "S_2") (pintype "bidirectional"))
    )
    (net (code "37") (name "Net-(U$1-DSG)") (class "Default")
      (node (ref "R17") (pin "2") (pinfunction "2_2") (pintype "passive"))
      (node (ref "U$1") (pin "1") (pinfunction "DSG_1") (pintype "bidirectional"))
      (node (ref "U$4") (pin "1") (pinfunction "G_1") (pintype "bidirectional"))
    )
    (net (code "38") (name "Net-(U$1-SRN)") (class "Default")
      (node (ref "C14") (pin "1") (pinfunction "1_1") (pintype "passive"))
      (node (ref "C16") (pin "2") (pinfunction "2_2") (pintype "passive"))
      (node (ref "R15") (pin "1") (pinfunction "1_1") (pintype "passive"))
      (node (ref "U$1") (pin "29") (pinfunction "SRN_29") (pintype "bidirectional"))
    )
    (net (code "39") (name "Net-(U$1-SRP)") (class "Default")
      (node (ref "C14") (pin "2") (pinfunction "2_2") (pintype "passive"))
      (node (ref "C15") (pin "1") (pinfunction "1_1") (pintype "passive"))
      (node (ref "R14") (pin "1") (pinfunction "1_1") (pintype "passive"))
      (node (ref "U$1") (pin "28") (pinfunction "SRP_28") (pintype "bidirectional"))
    )
    (net (code "40") (name "Net-(U$1-TS2)") (class "Default")
      (node (ref "R20") (pin "1") (pinfunction "1_1") (pintype "passive"))
      (node (ref "U$1") (pin "13") (pinfunction "TS2_13") (pintype "bidirectional"))
    )
    (net (code "41") (name "Net-(U$1-VC0)") (class "Default")
      (node (ref "C2") (pin "2") (pinfunction "2_2") (pintype "passive"))
      (node (ref "R2") (pin "1") (pinfunction "1_1") (pintype "passive"))
      (node (ref "U$1") (pin "27") (pinfunction "VC0_27") (pintype "bidirectional"))
    )
    (net (code "42") (name "Net-(U$1-VC1)") (class "Default")
      (node (ref "C3") (pin "1") (pinfunction "1_1") (pintype "passive"))
      (node (ref "C4") (pin "2") (pinfunction "2_2") (pintype "passive"))
      (node (ref "R3") (pin "1") (pinfunction "1_1") (pintype "passive"))
      (node (ref "U$1") (pin "26") (pinfunction "VC1_26") (pintype "bidirectional"))
    )
    (net (code "43") (name "Net-(U$1-VC2)") (class "Default")
      (node (ref "C4") (pin "1") (pinfunction "1_1") (pintype "passive"))
      (node (ref "C5") (pin "2") (pinfunction "2_2") (pintype "passive"))
      (node (ref "R4") (pin "1") (pinfunction "1_1") (pintype "passive"))
      (node (ref "U$1") (pin "25") (pinfunction "VC2_25") (pintype "bidirectional"))
    )
    (net (code "44") (name "Net-(U$1-VC3)") (class "Default")
      (node (ref "C5") (pin "1") (pinfunction "1_1") (pintype "passive"))
      (node (ref "C6") (pin "2") (pinfunction "2_2") (pintype "passive"))
      (node (ref "R5") (pin "1") (pinfunction "1_1") (pintype "passive"))
      (node (ref "U$1") (pin "24") (pinfunction "VC3_24") (pintype "bidirectional"))
    )
    (net (code "45") (name "Net-(U$1-VC4)") (class "Default")
      (node (ref "C6") (pin "1") (pinfunction "1_1") (pintype "passive"))
      (node (ref "C7") (pin "2") (pinfunction "2_2") (pintype "passive"))
      (node (ref "R6") (pin "1") (pinfunction "1_1") (pintype "passive"))
      (node (ref "U$1") (pin "23") (pinfunction "VC4_23") (pintype "bidirectional"))
    )
    (net (code "46") (name "Net-(U$1-VC5)") (class "Default")
      (node (ref "C7") (pin "1") (pinfunction "1_1") (pintype "passive"))
      (node (ref "R7") (pin "1") (pinfunction "1_1") (pintype "passive"))
      (node (ref "U$1") (pin "22") (pinfunction "VC5_22") (pintype "bidirectional"))
      (node (ref "U$2") (pin "P$1") (pinfunction "P$1_P$1") (pintype "bidirectional"))
    )
    (net (code "47") (name "Net-(U$1-VC5B)") (class "Default")
      (node (ref "C8") (pin "2") (pinfunction "2_2") (pintype "passive"))
      (node (ref "R13") (pin "1") (pinfunction "1_1") (pintype "passive"))
      (node (ref "U$1") (pin "21") (pinfunction "VC5B_21") (pintype "bidirectional"))
    )
    (net (code "48") (name "Net-(U$1-VC6)") (class "Default")
      (node (ref "C13") (pin "1") (pinfunction "1_1") (pintype "passive"))
      (node (ref "C9") (pin "2") (pinfunction "2_2") (pintype "passive"))
      (node (ref "R8") (pin "1") (pinfunction "1_1") (pintype "passive"))
      (node (ref "U$1") (pin "20") (pinfunction "VC6_20") (pintype "bidirectional"))
    )
    (net (code "49") (name "Net-(U$1-VC7)") (class "Default")
      (node (ref "C10") (pin "2") (pinfunction "2_2") (pintype "passive"))
      (node (ref "C9") (pin "1") (pinfunction "1_1") (pintype "passive"))
      (node (ref "R9") (pin "1") (pinfunction "1_1") (pintype "passive"))
      (node (ref "U$1") (pin "19") (pinfunction "VC7_19") (pintype "bidirectional"))
    )
    (net (code "50") (name "Net-(U$1-VC8)") (class "Default")
      (node (ref "C10") (pin "1") (pinfunction "1_1") (pintype "passive"))
      (node (ref "C11") (pin "2") (pinfunction "2_2") (pintype "passive"))
      (node (ref "R10") (pin "1") (pinfunction "1_1") (pintype "passive"))
      (node (ref "U$1") (pin "18") (pinfunction "VC8_18") (pintype "bidirectional"))
    )
    (net (code "51") (name "Net-(U$1-VC9)") (class "Default")
      (node (ref "C11") (pin "1") (pinfunction "1_1") (pintype "passive"))
      (node (ref "C12") (pin "2") (pinfunction "2_2") (pintype "passive"))
      (node (ref "R11") (pin "1") (pinfunction "1_1") (pintype "passive"))
      (node (ref "U$1") (pin "17") (pinfunction "VC9_17") (pintype "bidirectional"))
    )
    (net (code "52") (name "Net-(U$1-VC10)") (class "Default")
      (node (ref "C12") (pin "1") (pinfunction "1_1") (pintype "passive"))
      (node (ref "R12") (pin "1") (pinfunction "1_1") (pintype "passive"))
      (node (ref "U$1") (pin "16") (pinfunction "VC10_16") (pintype "bidirectional"))
      (node (ref "U$9") (pin "P$1") (pinfunction "P$1_P$1") (pintype "bidirectional"))
    )
    (net (code "53") (name "Net-(U$4-D)") (class "Default")
      (node (ref "R31") (pin "2") (pinfunction "2_2") (pintype "passive"))
      (node (ref "U$4") (pin "3") (pinfunction "D_3") (pintype "bidirectional"))
      (node (ref "U$5") (pin "3") (pinfunction "D_3") (pintype "bidirectional"))
    )
    (net (code "54") (name "Net-(U$4-S)") (class "Default")
      (node (ref "C17") (pin "2") (pinfunction "2_2") (pintype "passive"))
      (node (ref "R15") (pin "2") (pinfunction "2_2") (pintype "passive"))
      (node (ref "R17") (pin "1") (pinfunction "1_1") (pintype "passive"))
      (node (ref "R55") (pin "2") (pinfunction "2_2") (pintype "passive"))
      (node (ref "U$4") (pin "2") (pinfunction "S_2") (pintype "bidirectional"))
    )
    (net (code "55") (name "Net-(U$5-G)") (class "Default")
      (node (ref "R18") (pin "2") (pinfunction "2_2") (pintype "passive"))
      (node (ref "R19") (pin "1") (pinfunction "1_1") (pintype "passive"))
      (node (ref "U$5") (pin "1") (pinfunction "G_1") (pintype "bidirectional"))
      (node (ref "U$6") (pin "P$2") (pinfunction "P$2_P$2") (pintype "bidirectional"))
    )
    (net (code "56") (name "Net-(U$7-D)") (class "Default")
      (node (ref "R19") (pin "2") (pinfunction "2_2") (pintype "passive"))
      (node (ref "U$6") (pin "P$1") (pinfunction "P$1_P$1") (pintype "bidirectional"))
      (node (ref "U$7") (pin "3") (pinfunction "D_3") (pintype "bidirectional"))
    )
    (net (code "57") (name "Net-(U$8-D)") (class "Default")
      (node (ref "R31") (pin "1") (pinfunction "1_1") (pintype "passive"))
      (node (ref "U$8") (pin "3") (pinfunction "D_3") (pintype "bidirectional"))
    )
    (net (code "58") (name "Net-(U$10-BAT)") (class "Default")
      (node (ref "C22") (pin "1") (pinfunction "1_1") (pintype "passive"))
      (node (ref "R28") (pin "2") (pinfunction "2_2") (pintype "passive"))
      (node (ref "R29") (pin "1") (pinfunction "1_1") (pintype "passive"))
      (node (ref "U$10") (pin "7") (pinfunction "BAT_7") (pintype "bidirectional"))
    )
    (net (code "59") (name "Net-(U$10-LED1)") (class "Default")
      (node (ref "LED1") (pin "C") (pinfunction "C_C") (pintype "passive"))
      (node (ref "U$10") (pin "16") (pinfunction "LED1_16") (pintype "bidirectional"))
    )
    (net (code "60") (name "Net-(U$10-LED2)") (class "Default")
      (node (ref "LED2") (pin "C") (pinfunction "C_C") (pintype "passive"))
      (node (ref "U$10") (pin "17") (pinfunction "LED2_17") (pintype "bidirectional"))
    )
    (net (code "61") (name "Net-(U$10-LED3)") (class "Default")
      (node (ref "LED3") (pin "C") (pinfunction "C_C") (pintype "passive"))
      (node (ref "U$10") (pin "18") (pinfunction "LED3_18") (pintype "bidirectional"))
    )
    (net (code "62") (name "Net-(U$10-LED4)") (class "Default")
      (node (ref "LED4") (pin "C") (pinfunction "C_C") (pintype "passive"))
      (node (ref "U$10") (pin "19") (pinfunction "LED4_19") (pintype "bidirectional"))
    )
    (net (code "63") (name "Net-(U$10-LED5)") (class "Default")
      (node (ref "LED5") (pin "C") (pinfunction "C_C") (pintype "passive"))
      (node (ref "U$10") (pin "20") (pinfunction "LED5_20") (pintype "bidirectional"))
    )
    (net (code "64") (name "Net-(U$10-PRECHG)") (class "Default")
      (node (ref "R34") (pin "2") (pinfunction "2_2") (pintype "passive"))
      (node (ref "U$10") (pin "5") (pinfunction "PRECHG_5") (pintype "bidirectional"))
    )
    (net (code "65") (name "Net-(U$10-PWRM)") (class "Default")
      (node (ref "LED6") (pin "C") (pinfunction "C_C") (pintype "passive"))
      (node (ref "U$10") (pin "15") (pinfunction "PWRM_15") (pintype "bidirectional"))
    )
    (net (code "66") (name "Net-(U$10-RBI)") (class "Default")
      (node (ref "C24") (pin "2") (pinfunction "2_2") (pintype "passive"))
      (node (ref "U$10") (pin "27") (pinfunction "RBI_27") (pintype "bidirectional"))
    )
    (net (code "67") (name "Net-(U$10-SMBC)") (class "Default")
      (node (ref "R45") (pin "1") (pinfunction "1_1") (pintype "passive"))
      (node (ref "U$10") (pin "13") (pinfunction "SMBC_13") (pintype "bidirectional"))
    )
    (net (code "68") (name "Net-(U$10-SMBD)") (class "Default")
      (node (ref "R46") (pin "1") (pinfunction "1_1") (pintype "passive"))
      (node (ref "U$10") (pin "11") (pinfunction "SMBD_11") (pintype "bidirectional"))
    )
    (net (code "69") (name "Net-(U$10-VEN)") (class "Default")
      (node (ref "R26") (pin "1") (pinfunction "1_1") (pintype "passive"))
      (node (ref "U$10") (pin "12") (pinfunction "VEN_12") (pintype "bidirectional"))
      (node (ref "U$12") (pin "1") (pinfunction "G_1") (pintype "bidirectional"))
    )
    (net (code "70") (name "Net-(U$11-D)") (class "Default")
      (node (ref "R28") (pin "1") (pinfunction "1_1") (pintype "passive"))
      (node (ref "U$11") (pin "3") (pinfunction "D_3") (pintype "bidirectional"))
    )
    (net (code "71") (name "Net-(U$11-G)") (class "Default")
      (node (ref "R1") (pin "2") (pinfunction "2_2") (pintype "passive"))
      (node (ref "R27") (pin "1") (pinfunction "1_1") (pintype "passive"))
      (node (ref "U$11") (pin "1") (pinfunction "G_1") (pintype "bidirectional"))
      (node (ref "U$13") (pin "P$1") (pinfunction "1_P$1") (pintype "bidirectional"))
    )
    (net (code "72") (name "Net-(U$12-D)") (class "Default")
      (node (ref "R27") (pin "2") (pinfunction "2_2") (pintype "passive"))
      (node (ref "U$12") (pin "3") (pinfunction "D_3") (pintype "bidirectional"))
    )
    (net (code "73") (name "Net-(U$14-2)") (class "Default")
      (node (ref "R32") (pin "2") (pinfunction "2_2") (pintype "passive"))
      (node (ref "R33") (pin "2") (pinfunction "2_2") (pintype "passive"))
      (node (ref "U$14") (pin "P$2") (pinfunction "2_P$2") (pintype "bidirectional"))
      (node (ref "U$8") (pin "1") (pinfunction "G_1") (pintype "bidirectional"))
    )
    (net (code "74") (name "Net-(U$20-P0_6)") (class "Default")
      (node (ref "LED8") (pin "A") (pinfunction "A_A") (pintype "passive"))
      (node (ref "U$20") (pin "27") (pinfunction "P0_6_27") (pintype "bidirectional"))
    )
    (net (code "75") (name "Net-(U$20-P0_7)") (class "Default")
      (node (ref "LED7") (pin "A") (pinfunction "A_A") (pintype "passive"))
      (node (ref "U$20") (pin "26") (pinfunction "P0_7_26") (pintype "bidirectional"))
    )
    (net (code "76") (name "Net-(U$20-P1_1)") (class "Default")
      (node (ref "JP4") (pin "1") (pinfunction "1_1") (pintype "passive"))
      (node (ref "U$20") (pin "23") (pinfunction "P1_1_23") (pintype "bidirectional"))
    )
    (net (code "77") (name "Net-(U$20-P1_7)") (class "Default")
      (node (ref "JP1") (pin "2") (pinfunction "2_2") (pintype "passive"))
      (node (ref "R60") (pin "1") (pinfunction "1_1") (pintype "passive"))
      (node (ref "U$20") (pin "12") (pinfunction "P1_7_12") (pintype "bidirectional"))
    )
    (net (code "78") (name "Net-(U$20-RESET#)") (class "Default")
      (node (ref "U$20") (pin "34") (pinfunction "RESET#_34") (pintype "bidirectional"))
      (node (ref "U$22") (pin "7") (pinfunction "7A_7") (pintype "bidirectional"))
    )
    (net (code "79") (name "Net-(U$21-BYPASS)") (class "Default")
      (node (ref "C31") (pin "1") (pinfunction "1_1") (pintype "passive"))
      (node (ref "U$21") (pin "4") (pinfunction "BYPASS_4") (pintype "bidirectional"))
    )
    (net (code "80") (name "Net-(U$21-VOUT)") (class "Default")
      (node (ref "C32") (pin "1") (pinfunction "1_1") (pintype "passive"))
      (node (ref "U$21") (pin "5") (pinfunction "VOUT_5") (pintype "bidirectional"))
      (node (ref "U$23") (pin "1") (pinfunction "1_1") (pintype "bidirectional"))
    )
    (net (code "81") (name "Net-(U$25-CAP)") (class "Default")
      (node (ref "C41") (pin "2") (pinfunction "2_2") (pintype "passive"))
      (node (ref "U$25") (pin "2") (pinfunction "CAP_2") (pintype "bidirectional"))
    )
    (net (code "82") (name "Net-(U$26-D)") (class "Default")
      (node (ref "R35") (pin "2") (pinfunction "2_2") (pintype "passive"))
      (node (ref "U$26") (pin "3") (pinfunction "D_3") (pintype "bidirectional"))
    )
    (net (code "83") (name "Net-(U$26-G)") (class "Default")
      (node (ref "R16") (pin "2") (pinfunction "2_2") (pintype "passive"))
      (node (ref "U$26") (pin "1") (pinfunction "G_1") (pintype "bidirectional"))
    )
    (net (code "84") (name "Net-(U$26-S)") (class "Default")
      (node (ref "R51") (pin "1") (pinfunction "1_1") (pintype "passive"))
      (node (ref "U$26") (pin "2") (pinfunction "S_2") (pintype "bidirectional"))
      (node (ref "U$27") (pin "P$1") (pinfunction "P$1_P$1") (pintype "bidirectional"))
    )
    (net (code "85") (name "Net-(U$32-BYP)") (class "Default")
      (node (ref "C40") (pin "1") (pinfunction "1_1") (pintype "passive"))
      (node (ref "U$32") (pin "P$4") (pinfunction "BYP_P$4") (pintype "bidirectional"))
    )
    (net (code "86") (name "Net-(U$34-RST_B)") (class "Default")
      (node (ref "R56") (pin "1") (pinfunction "1_1") (pintype "passive"))
      (node (ref "U$34") (pin "4") (pinfunction "RST_B_4") (pintype "bidirectional"))
    )
    (net (code "87") (name "Net-(U$34-VREGD)") (class "Default")
      (node (ref "C34") (pin "1") (pinfunction "1_1") (pintype "passive"))
      (node (ref "U$34") (pin "16") (pinfunction "VREGD_16") (pintype "bidirectional"))
    )
    (net (code "88") (name "P2_1") (class "Default")
      (node (ref "U$20") (pin "10") (pinfunction "P2_1_10") (pintype "bidirectional"))
      (node (ref "U$22") (pin "4") (pinfunction "4A_4") (pintype "bidirectional"))
    )
    (net (code "89") (name "P2_2") (class "Default")
      (node (ref "U$20") (pin "9") (pinfunction "P2_2_9") (pintype "bidirectional"))
      (node (ref "U$22") (pin "3") (pinfunction "3A_3") (pintype "bidirectional"))
    )
    (net (code "90") (name "PACK+") (class "Default")
      (node (ref "C27") (pin "2") (pinfunction "2_2") (pintype "passive"))
      (node (ref "U$28") (pin "P$1") (pinfunction "P$1_P$1") (pintype "bidirectional"))
      (node (ref "U$29") (pin "2") (pinfunction "P$2_2") (pintype "bidirectional"))
      (node (ref "U$31") (pin "P$2") (pinfunction "2_P$2") (pintype "bidirectional"))
      (node (ref "U$35") (pin "P$1") (pinfunction "P$1_P$1") (pintype "bidirectional"))
      (node (ref "U$36") (pin "P$1") (pinfunction "P$1_P$1") (pintype "bidirectional"))
      (node (ref "U$39") (pin "P$1") (pinfunction "P$1_P$1") (pintype "bidirectional"))
    )
    (net (code "91") (name "PACK-") (class "Default")
      (node (ref "C18") (pin "1") (pinfunction "1_1") (pintype "passive"))
      (node (ref "C26") (pin "1") (pinfunction "1_1") (pintype "passive"))
      (node (ref "R18") (pin "1") (pinfunction "1_1") (pintype "passive"))
      (node (ref "R32") (pin "1") (pinfunction "1_1") (pintype "passive"))
      (node (ref "U$14") (pin "P$1") (pinfunction "1_P$1") (pintype "bidirectional"))
      (node (ref "U$28") (pin "P$2") (pinfunction "P$2_P$2") (pintype "bidirectional"))
      (node (ref "U$29") (pin "1") (pinfunction "P$1_1") (pintype "bidirectional"))
      (node (ref "U$30") (pin "P$1") (pinfunction "P$1_P$1") (pintype "bidirectional"))
      (node (ref "U$37") (pin "P$1") (pinfunction "P$1_P$1") (pintype "bidirectional"))
      (node (ref "U$38") (pin "P$1") (pinfunction "P$1_P$1") (pintype "bidirectional"))
      (node (ref "U$5") (pin "2") (pinfunction "S_2") (pintype "bidirectional"))
      (node (ref "U$8") (pin "2") (pinfunction "S_2") (pintype "bidirectional"))
    )
    (net (code "92") (name "REGOUT") (class "Default")
      (node (ref "C23") (pin "2") (pinfunction "2_2") (pintype "passive"))
      (node (ref "C44") (pin "2") (pinfunction "2_2") (pintype "passive"))
      (node (ref "Q1") (pin "2") (pinfunction "E_2") (pintype "bidirectional"))
      (node (ref "R22") (pin "1") (pinfunction "1_1") (pintype "passive"))
      (node (ref "R23") (pin "1") (pinfunction "1_1") (pintype "passive"))
      (node (ref "R26") (pin "2") (pinfunction "2_2") (pintype "passive"))
      (node (ref "R36") (pin "1") (pinfunction "1_1") (pintype "passive"))
      (node (ref "R38") (pin "1") (pinfunction "1_1") (pintype "passive"))
      (node (ref "R39") (pin "1") (pinfunction "1_1") (pintype "passive"))
      (node (ref "R40") (pin "1") (pinfunction "1_1") (pintype "passive"))
      (node (ref "R41") (pin "1") (pinfunction "1_1") (pintype "passive"))
      (node (ref "R42") (pin "1") (pinfunction "1_1") (pintype "passive"))
      (node (ref "R43") (pin "1") (pinfunction "1_1") (pintype "passive"))
      (node (ref "R44") (pin "1") (pinfunction "1_1") (pintype "passive"))
      (node (ref "U$1") (pin "8") (pinfunction "REGOUT_8") (pintype "bidirectional"))
      (node (ref "U$10") (pin "26") (pinfunction "VCC_26") (pintype "bidirectional"))
      (node (ref "U$23") (pin "3") (pinfunction "3_3") (pintype "bidirectional"))
    )
    (net (code "93") (name "REGSRC") (class "Default")
      (node (ref "C25") (pin "2") (pinfunction "2_2") (pintype "passive"))
      (node (ref "R51") (pin "2") (pinfunction "2_2") (pintype "passive"))
      (node (ref "U$1") (pin "9") (pinfunction "REGSRC_9") (pintype "bidirectional"))
      (node (ref "U$27") (pin "P$2") (pinfunction "P$2_P$2") (pintype "bidirectional"))
    )
    (net (code "94") (name "SCL") (class "Default")
      (node (ref "JP5") (pin "2") (pinfunction "2_2") (pintype "passive"))
      (node (ref "R52") (pin "2") (pinfunction "2_2") (pintype "passive"))
      (node (ref "R57") (pin "1") (pinfunction "1_1") (pintype "passive"))
      (node (ref "U$20") (pin "14") (pinfunction "SCL_14") (pintype "bidirectional"))
      (node (ref "U$25") (pin "8") (pinfunction "SCL_8") (pintype "bidirectional"))
      (node (ref "U$32") (pin "P$2") (pinfunction "SCL_P$2") (pintype "bidirectional"))
      (node (ref "U$34") (pin "11") (pinfunction "SCL/SCLK_11") (pintype "bidirectional"))
    )
    (net (code "95") (name "SCL_") (class "Default")
      (node (ref "R22") (pin "2") (pinfunction "2_2") (pintype "passive"))
      (node (ref "U$1") (pin "5") (pinfunction "SCL_5") (pintype "bidirectional"))
      (node (ref "U$10") (pin "4") (pinfunction "SCL_4") (pintype "bidirectional"))
    )
    (net (code "96") (name "SDA") (class "Default")
      (node (ref "JP5") (pin "3") (pinfunction "3_3") (pintype "passive"))
      (node (ref "R53") (pin "2") (pinfunction "2_2") (pintype "passive"))
      (node (ref "R58") (pin "1") (pinfunction "1_1") (pintype "passive"))
      (node (ref "U$20") (pin "15") (pinfunction "SDA_15") (pintype "bidirectional"))
      (node (ref "U$25") (pin "7") (pinfunction "SDA_7") (pintype "bidirectional"))
      (node (ref "U$32") (pin "P$10") (pinfunction "SDA_P$10") (pintype "bidirectional"))
      (node (ref "U$34") (pin "12") (pinfunction "SDA/MOSI_12") (pintype "bidirectional"))
    )
    (net (code "97") (name "SDA_") (class "Default")
      (node (ref "R23") (pin "2") (pinfunction "2_2") (pintype "passive"))
      (node (ref "U$1") (pin "4") (pinfunction "SDA_4") (pintype "bidirectional"))
      (node (ref "U$10") (pin "3") (pinfunction "SDA_3") (pintype "bidirectional"))
    )
    (net (code "98") (name "SENSOR_POWER") (class "Default")
      (node (ref "C33") (pin "1") (pinfunction "1_1") (pintype "passive"))
      (node (ref "C35") (pin "1") (pinfunction "1_1") (pintype "passive"))
      (node (ref "C36") (pin "1") (pinfunction "1_1") (pintype "passive"))
      (node (ref "C37") (pin "1") (pinfunction "1_1") (pintype "passive"))
      (node (ref "C38") (pin "1") (pinfunction "1_1") (pintype "passive"))
      (node (ref "C39") (pin "1") (pinfunction "1_1") (pintype "passive"))
      (node (ref "C42") (pin "2") (pinfunction "2_2") (pintype "passive"))
      (node (ref "C43") (pin "1") (pinfunction "1_1") (pintype "passive"))
      (node (ref "R56") (pin "2") (pinfunction "2_2") (pintype "passive"))
      (node (ref "U$25") (pin "1") (pinfunction "VDD_1") (pintype "bidirectional"))
      (node (ref "U$25") (pin "4") (pinfunction "VDDIO_4") (pintype "bidirectional"))
      (node (ref "U$32") (pin "P$1") (pinfunction "VDD_P$1") (pintype "bidirectional"))
      (node (ref "U$32") (pin "P$8") (pinfunction "VDDIO_P$8") (pintype "bidirectional"))
      (node (ref "U$34") (pin "15") (pinfunction "VDD_15") (pintype "bidirectional"))
      (node (ref "U$34") (pin "17") (pinfunction "SPI_CSB_17") (pintype "bidirectional"))
      (node (ref "U$34") (pin "18") (pinfunction "VDDIO_18") (pintype "bidirectional"))
    )
    (net (code "99") (name "SMBC") (class "Default")
      (node (ref "R47") (pin "2") (pinfunction "2_2") (pintype "passive"))
      (node (ref "R52") (pin "1") (pinfunction "1_1") (pintype "passive"))
      (node (ref "U$19") (pin "P$2") (pinfunction "P$2_P$2") (pintype "bidirectional"))
    )
    (net (code "100") (name "SMBD") (class "Default")
      (node (ref "R48") (pin "2") (pinfunction "2_2") (pintype "passive"))
      (node (ref "R53") (pin "1") (pinfunction "1_1") (pintype "passive"))
      (node (ref "U$18") (pin "P$2") (pinfunction "P$2_P$2") (pintype "bidirectional"))
    )
    (net (code "101") (name "VC5X") (class "Default")
      (node (ref "C1") (pin "1") (pinfunction "1_1") (pintype "passive"))
      (node (ref "C13") (pin "2") (pinfunction "2_2") (pintype "passive"))
      (node (ref "C19") (pin "1") (pinfunction "1_1") (pintype "passive"))
      (node (ref "C21") (pin "2") (pinfunction "2_2") (pintype "passive"))
      (node (ref "C8") (pin "1") (pinfunction "1_1") (pintype "passive"))
      (node (ref "R16") (pin "1") (pinfunction "1_1") (pintype "passive"))
      (node (ref "R20") (pin "2") (pinfunction "2_2") (pintype "passive"))
      (node (ref "R24") (pin "1") (pinfunction "1_1") (pintype "passive"))
      (node (ref "U$1") (pin "10") (pinfunction "VC5X_10") (pintype "bidirectional"))
      (node (ref "U$2") (pin "P$2") (pinfunction "P$2_P$2") (pintype "bidirectional"))
    )
    (net (code "102") (name "VC10X") (class "Default")
      (node (ref "C1") (pin "2") (pinfunction "2_2") (pintype "passive"))
      (node (ref "R30") (pin "1") (pinfunction "1_1") (pintype "passive"))
      (node (ref "U$1") (pin "15") (pinfunction "BAT_15") (pintype "bidirectional"))
      (node (ref "U$9") (pin "P$2") (pinfunction "P$2_P$2") (pintype "bidirectional"))
    )
    (net (code "103") (name "unconnected-(U$10-ADREN-Pad29)") (class "Default")
      (node (ref "U$10") (pin "29") (pinfunction "ADREN_29") (pintype "bidirectional"))
    )
    (net (code "104") (name "unconnected-(U$10-COM-Pad1)") (class "Default")
      (node (ref "U$10") (pin "1") (pinfunction "COM_1") (pintype "bidirectional"))
    )
    (net (code "105") (name "unconnected-(U$10-SAFE-Pad10)") (class "Default")
      (node (ref "U$10") (pin "10") (pinfunction "SAFE_10") (pintype "bidirectional"))
    )
    (net (code "106") (name "unconnected-(U$20-NC-Pad16)") (class "Default")
      (node (ref "U$20") (pin "16") (pinfunction "NC_16") (pintype "bidirectional"))
    )
    (net (code "107") (name "unconnected-(U$20-NC2-Pad35)") (class "Default")
      (node (ref "U$20") (pin "35") (pinfunction "NC2_35") (pintype "bidirectional"))
    )
    (net (code "108") (name "unconnected-(U$20-P0_0-Pad33)") (class "Default")
      (node (ref "U$20") (pin "33") (pinfunction "P0_0_33") (pintype "bidirectional"))
    )
    (net (code "109") (name "unconnected-(U$20-P0_1-Pad32)") (class "Default")
      (node (ref "U$20") (pin "32") (pinfunction "P0_1_32") (pintype "bidirectional"))
    )
    (net (code "110") (name "unconnected-(U$20-P0_2-Pad31)") (class "Default")
      (node (ref "U$20") (pin "31") (pinfunction "P0_2_31") (pintype "bidirectional"))
    )
    (net (code "111") (name "unconnected-(U$20-P0_3-Pad30)") (class "Default")
      (node (ref "U$20") (pin "30") (pinfunction "P0_3_30") (pintype "bidirectional"))
    )
    (net (code "112") (name "unconnected-(U$20-P0_4-Pad29)") (class "Default")
      (node (ref "U$20") (pin "29") (pinfunction "P0_4_29") (pintype "bidirectional"))
    )
    (net (code "113") (name "unconnected-(U$20-P0_5-Pad28)") (class "Default")
      (node (ref "U$20") (pin "28") (pinfunction "P0_5_28") (pintype "bidirectional"))
    )
    (net (code "114") (name "unconnected-(U$20-P1_0-Pad24)") (class "Default")
      (node (ref "U$20") (pin "24") (pinfunction "P1_0_24") (pintype "bidirectional"))
    )
    (net (code "115") (name "unconnected-(U$20-P1_2-Pad22)") (class "Default")
      (node (ref "U$20") (pin "22") (pinfunction "P1_2_22") (pintype "bidirectional"))
    )
    (net (code "116") (name "unconnected-(U$20-P1_3-Pad21)") (class "Default")
      (node (ref "U$20") (pin "21") (pinfunction "P1_3_21") (pintype "bidirectional"))
    )
    (net (code "117") (name "unconnected-(U$20-P1_4-Pad20)") (class "Default")
      (node (ref "U$20") (pin "20") (pinfunction "P1_4_20") (pintype "bidirectional"))
    )
    (net (code "118") (name "unconnected-(U$20-P1_5-Pad19)") (class "Default")
      (node (ref "U$20") (pin "19") (pinfunction "P1_5_19") (pintype "bidirectional"))
    )
    (net (code "119") (name "unconnected-(U$20-P1_6-Pad13)") (class "Default")
      (node (ref "U$20") (pin "13") (pinfunction "P1_6_13") (pintype "bidirectional"))
    )
    (net (code "120") (name "unconnected-(U$20-P2_0-Pad11)") (class "Default")
      (node (ref "U$20") (pin "11") (pinfunction "P2_0_11") (pintype "bidirectional"))
    )
    (net (code "121") (name "unconnected-(U$22-5A-Pad5)") (class "Default")
      (node (ref "U$22") (pin "5") (pinfunction "5A_5") (pintype "bidirectional"))
    )
    (net (code "122") (name "unconnected-(U$22-6A-Pad6)") (class "Default")
      (node (ref "U$22") (pin "6") (pinfunction "6A_6") (pintype "bidirectional"))
    )
    (net (code "123") (name "unconnected-(U$22-8A-Pad8)") (class "Default")
      (node (ref "U$22") (pin "8") (pinfunction "8A_8") (pintype "bidirectional"))
    )
    (net (code "124") (name "unconnected-(U$22-9A-Pad9)") (class "Default")
      (node (ref "U$22") (pin "9") (pinfunction "9A_9") (pintype "bidirectional"))
    )
    (net (code "125") (name "unconnected-(U$22-10A-Pad10)") (class "Default")
      (node (ref "U$22") (pin "10") (pinfunction "10A_10") (pintype "bidirectional"))
    )
    (net (code "126") (name "unconnected-(U$24-Pad6)") (class "Default")
      (node (ref "U$24") (pin "6") (pinfunction "6_6") (pintype "bidirectional"))
    )
    (net (code "127") (name "unconnected-(U$24-PadA1)") (class "Default")
      (node (ref "U$24") (pin "A1") (pinfunction "A1_A1") (pintype "bidirectional"))
    )
    (net (code "128") (name "unconnected-(U$24-PadA2)") (class "Default")
      (node (ref "U$24") (pin "A2") (pinfunction "A2_A2") (pintype "bidirectional"))
    )
    (net (code "129") (name "unconnected-(U$25-INT1-Pad6)") (class "Default")
      (node (ref "U$25") (pin "6") (pinfunction "INT1_6") (pintype "bidirectional"))
    )
    (net (code "130") (name "unconnected-(U$25-INT2-Pad5)") (class "Default")
      (node (ref "U$25") (pin "5") (pinfunction "INT2_5") (pintype "bidirectional"))
    )
    (net (code "131") (name "unconnected-(U$32-INT1-PadP$3)") (class "Default")
      (node (ref "U$32") (pin "P$3") (pinfunction "INT1_P$3") (pintype "bidirectional"))
    )
    (net (code "132") (name "unconnected-(U$32-INT2-PadP$5)") (class "Default")
      (node (ref "U$32") (pin "P$5") (pinfunction "INT2_P$5") (pintype "bidirectional"))
    )
    (net (code "133") (name "unconnected-(U$33-PadA1)") (class "Default")
      (node (ref "U$33") (pin "A1") (pinfunction "A1_A1") (pintype "bidirectional"))
    )
    (net (code "134") (name "unconnected-(U$33-PadA2)") (class "Default")
      (node (ref "U$33") (pin "A2") (pinfunction "A2_A2") (pintype "bidirectional"))
    )
    (net (code "135") (name "unconnected-(U$34-INT1-Pad3)") (class "Default")
      (node (ref "U$34") (pin "3") (pinfunction "INT1_3") (pintype "bidirectional"))
    )
    (net (code "136") (name "unconnected-(U$34-INT2{slash}PWR_CTRL-Pad2)") (class "Default")
      (node (ref "U$34") (pin "2") (pinfunction "INT2/PWR_CTRL_2") (pintype "bidirectional"))
    )
  )
)
